# backplane.net
KiCad netlist of a schematic drawn in EAGLE
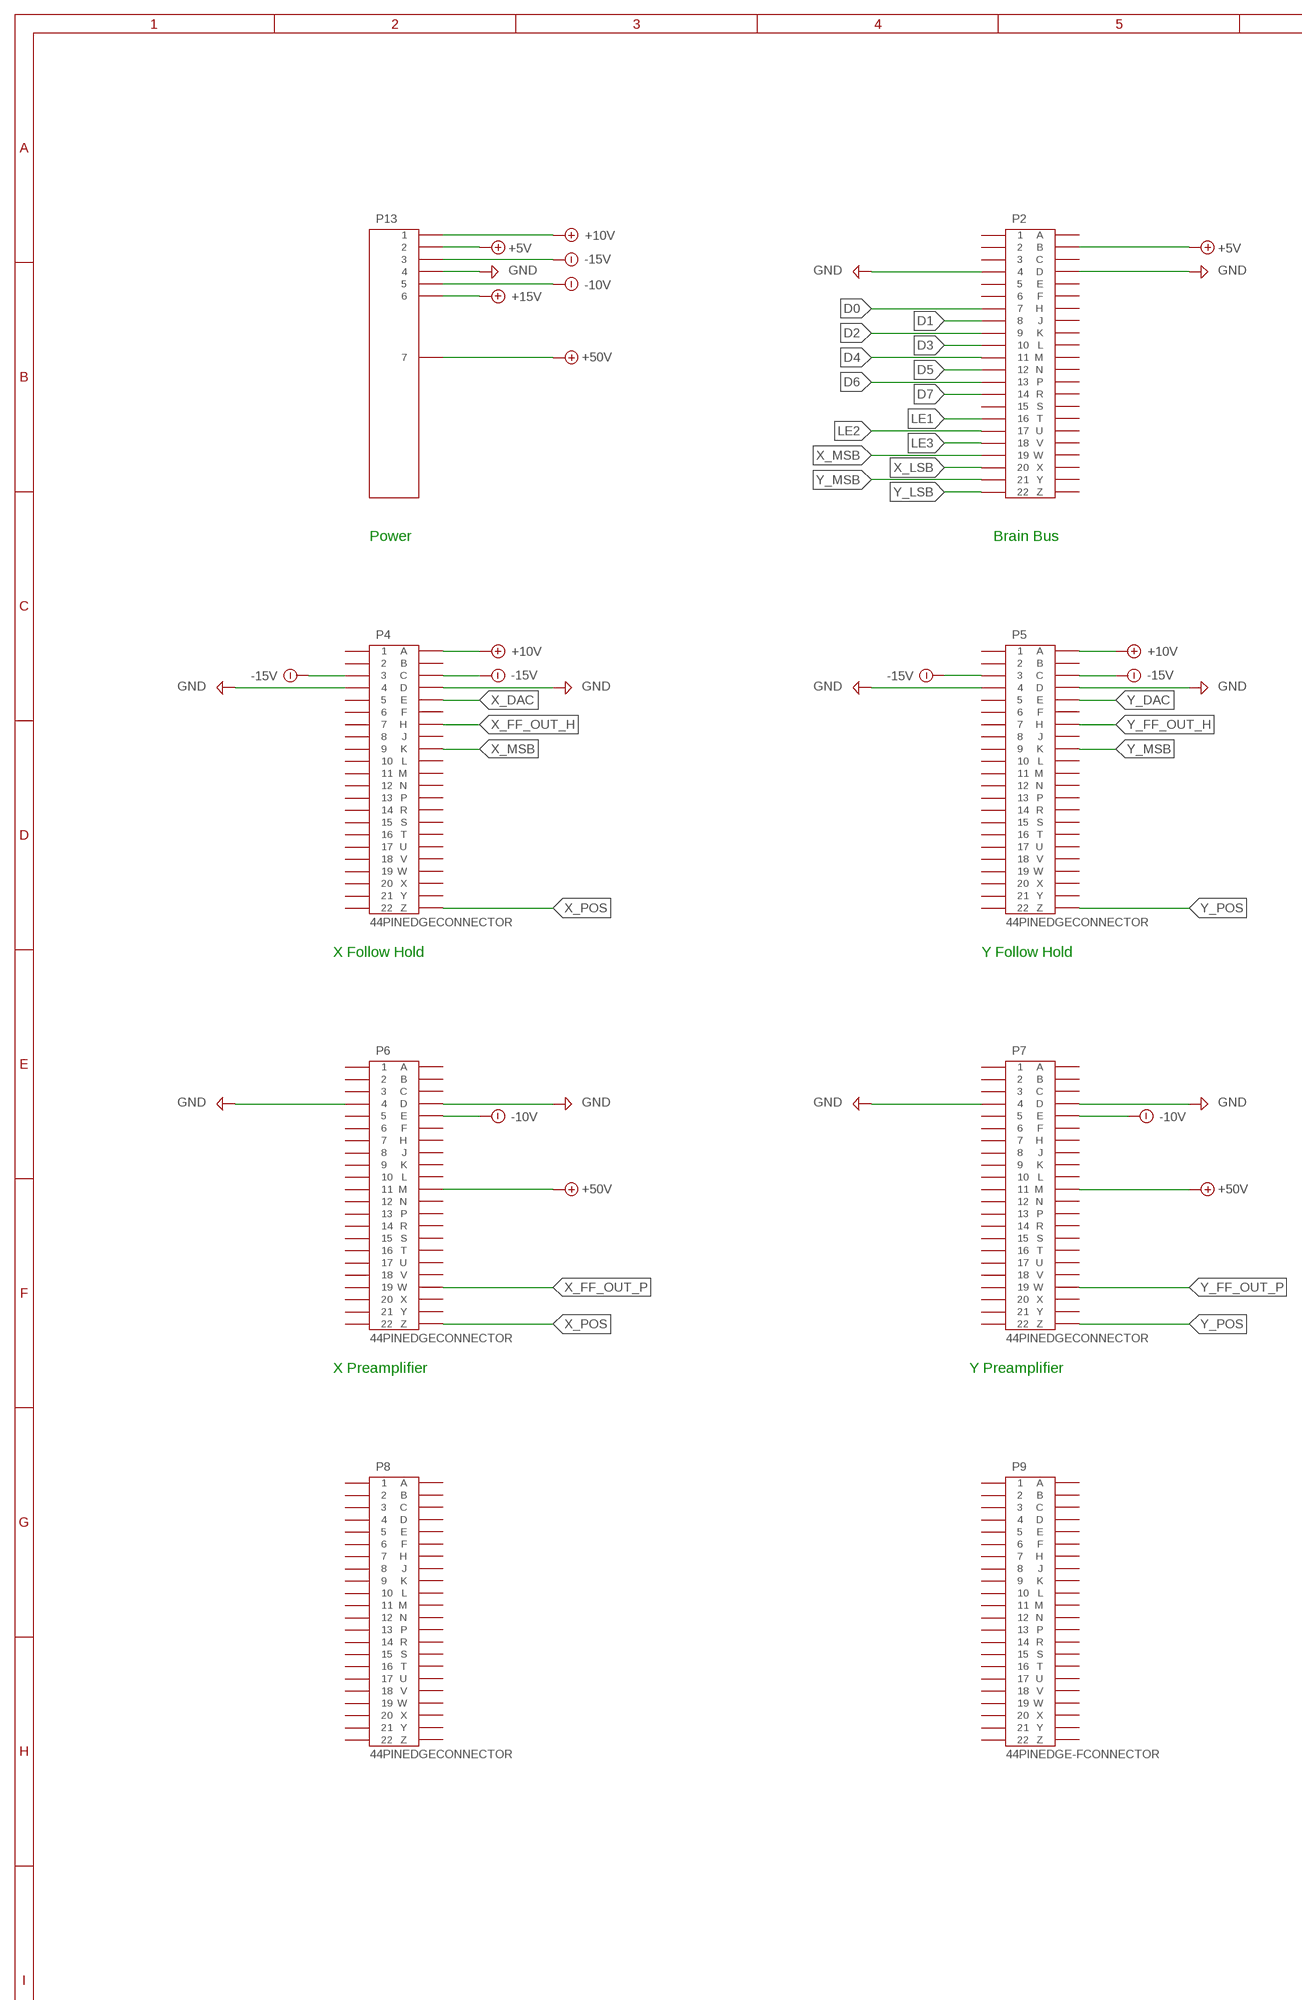
[diagram p0: schematic, sheet 1, part 1 of 2]
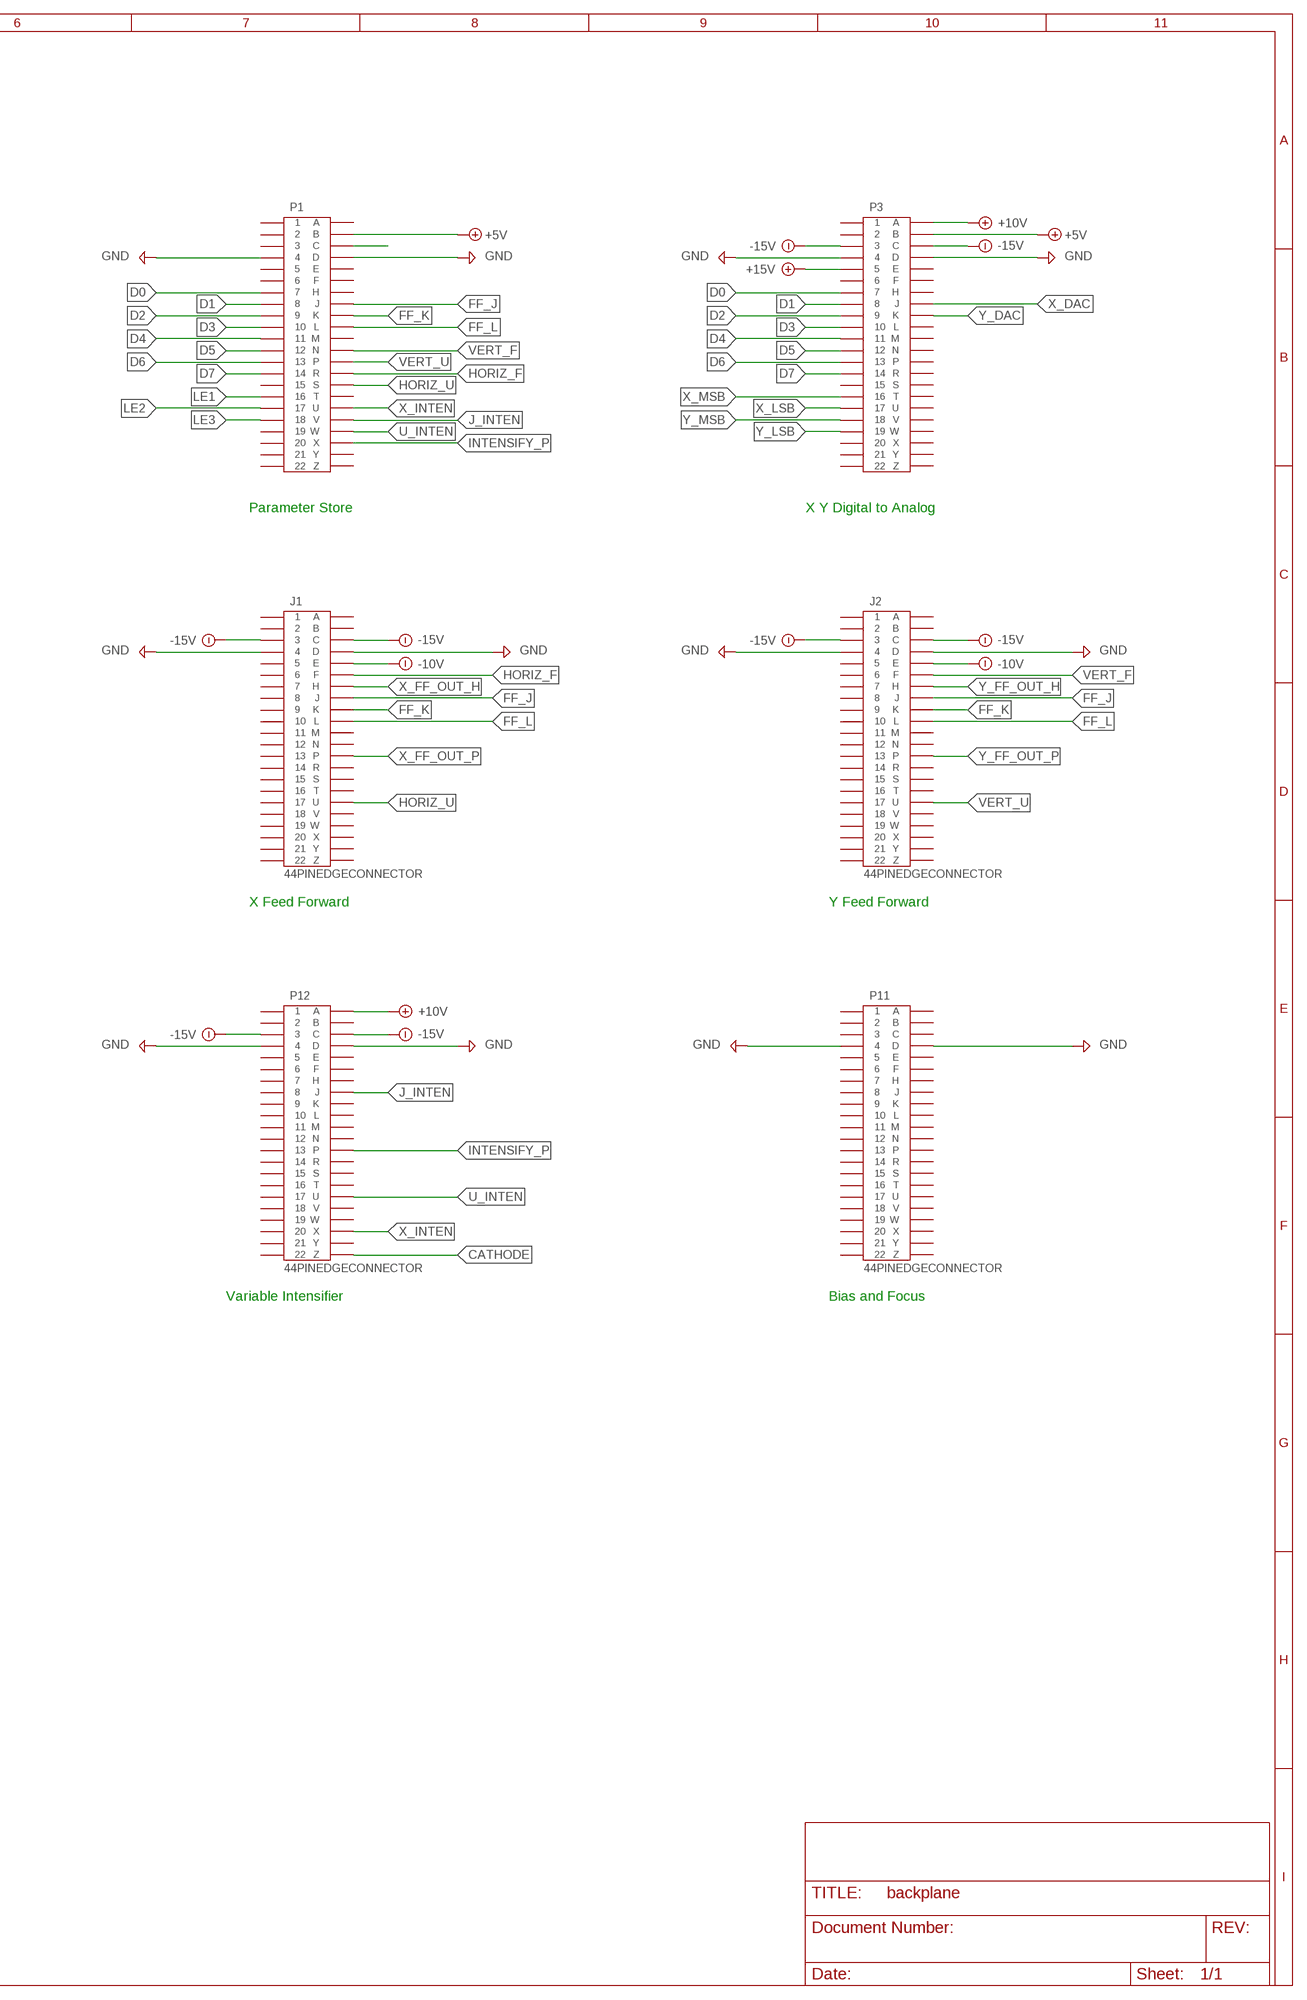
[diagram p1: schematic, sheet 1, part 2 of 2]

(export (version "E")
  (design (tool "Eeschema 10.0.6"))
  (components
    (comp (ref "J1")
      (value "44PINEDGECONNECTOR")
      (footprint "eagle-import:44PINEDGECONN")
      (libsource (lib "eagle-import") (part "44PINEDGECONNECTOR"))
    )
    (comp (ref "J2")
      (value "44PINEDGECONNECTOR")
      (footprint "eagle-import:44PINEDGECONN")
      (libsource (lib "eagle-import") (part "44PINEDGECONNECTOR"))
    )
    (comp (ref "P1")
      (value "44PINEDGECONNECTOR")
      (footprint "eagle-import:44PINEDGECONN")
      (libsource (lib "eagle-import") (part "44PINEDGECONNECTOR"))
    )
    (comp (ref "P2")
      (value "44PINEDGECONNECTOR")
      (footprint "eagle-import:44PINEDGECONN")
      (libsource (lib "eagle-import") (part "44PINEDGECONNECTOR"))
    )
    (comp (ref "P3")
      (value "44PINEDGECONNECTOR")
      (footprint "eagle-import:44PINEDGECONN")
      (libsource (lib "eagle-import") (part "44PINEDGECONNECTOR"))
    )
    (comp (ref "P4")
      (value "44PINEDGECONNECTOR")
      (footprint "eagle-import:44PINEDGECONN")
      (libsource (lib "eagle-import") (part "44PINEDGECONNECTOR"))
    )
    (comp (ref "P5")
      (value "44PINEDGECONNECTOR")
      (footprint "eagle-import:44PINEDGECONN")
      (libsource (lib "eagle-import") (part "44PINEDGECONNECTOR"))
    )
    (comp (ref "P6")
      (value "44PINEDGECONNECTOR")
      (footprint "eagle-import:44PINEDGECONN")
      (libsource (lib "eagle-import") (part "44PINEDGECONNECTOR"))
    )
    (comp (ref "P7")
      (value "44PINEDGECONNECTOR")
      (footprint "eagle-import:44PINEDGECONN")
      (libsource (lib "eagle-import") (part "44PINEDGECONNECTOR"))
    )
    (comp (ref "P8")
      (value "44PINEDGECONNECTOR")
      (footprint "eagle-import:44PINEDGECONN")
      (libsource (lib "eagle-import") (part "44PINEDGECONNECTOR"))
    )
    (comp (ref "P9")
      (value "44PINEDGE-FCONNECTOR")
      (footprint "eagle-import:44PINEDGECONN")
      (libsource (lib "eagle-import") (part "44PINEDGE-FCONNECTOR"))
    )
    (comp (ref "P11")
      (value "44PINEDGECONNECTOR")
      (footprint "eagle-import:44PINEDGECONN")
      (libsource (lib "eagle-import") (part "44PINEDGECONNECTOR"))
    )
    (comp (ref "P12")
      (value "44PINEDGECONNECTOR")
      (footprint "eagle-import:44PINEDGECONN")
      (libsource (lib "eagle-import") (part "44PINEDGECONNECTOR"))
    )
    (comp (ref "P13")
      (value "PASSTHROUGH")
      (footprint "eagle-import:PASSTHROUGH")
      (libsource (lib "eagle-import") (part "PASSTHROUGH"))
    )
  )
  (nets
    (net (code "1") (name "+5V") (class "Default")
      (node (ref "P1") (pin "P$24") (pinfunction "B_P$24") (pintype "passive"))
      (node (ref "P13") (pin "P$2") (pinfunction "2_P$2") (pintype "passive"))
      (node (ref "P2") (pin "P$24") (pinfunction "B_P$24") (pintype "passive"))
      (node (ref "P3") (pin "P$24") (pinfunction "B_P$24") (pintype "passive"))
    )
    (net (code "2") (name "+10V") (class "Default")
      (node (ref "P12") (pin "P$23") (pinfunction "A_P$23") (pintype "passive"))
      (node (ref "P13") (pin "P$1") (pinfunction "1_P$1") (pintype "passive"))
      (node (ref "P3") (pin "P$23") (pinfunction "A_P$23") (pintype "passive"))
      (node (ref "P4") (pin "P$23") (pinfunction "A_P$23") (pintype "passive"))
      (node (ref "P5") (pin "P$23") (pinfunction "A_P$23") (pintype "passive"))
    )
    (net (code "3") (name "+15V") (class "Default")
      (node (ref "P13") (pin "P$6") (pinfunction "6_P$6") (pintype "passive"))
      (node (ref "P3") (pin "P$5") (pinfunction "5_P$5") (pintype "passive"))
    )
    (net (code "4") (name "+50V") (class "Default")
      (node (ref "P13") (pin "P$7") (pinfunction "7_P$7") (pintype "passive"))
      (node (ref "P6") (pin "P$33") (pinfunction "M_P$33") (pintype "passive"))
      (node (ref "P7") (pin "P$33") (pinfunction "M_P$33") (pintype "passive"))
    )
    (net (code "5") (name "-10V") (class "Default")
      (node (ref "J1") (pin "P$27") (pinfunction "E_P$27") (pintype "passive"))
      (node (ref "J2") (pin "P$27") (pinfunction "E_P$27") (pintype "passive"))
      (node (ref "P13") (pin "P$5") (pinfunction "5_P$5") (pintype "passive"))
      (node (ref "P6") (pin "P$27") (pinfunction "E_P$27") (pintype "passive"))
      (node (ref "P7") (pin "P$27") (pinfunction "E_P$27") (pintype "passive"))
    )
    (net (code "6") (name "-15V") (class "Default")
      (node (ref "J1") (pin "P$25") (pinfunction "C_P$25") (pintype "passive"))
      (node (ref "J1") (pin "P$3") (pinfunction "3_P$3") (pintype "passive"))
      (node (ref "J2") (pin "P$25") (pinfunction "C_P$25") (pintype "passive"))
      (node (ref "J2") (pin "P$3") (pinfunction "3_P$3") (pintype "passive"))
      (node (ref "P12") (pin "P$25") (pinfunction "C_P$25") (pintype "passive"))
      (node (ref "P12") (pin "P$3") (pinfunction "3_P$3") (pintype "passive"))
      (node (ref "P13") (pin "P$3") (pinfunction "3_P$3") (pintype "passive"))
      (node (ref "P3") (pin "P$25") (pinfunction "C_P$25") (pintype "passive"))
      (node (ref "P3") (pin "P$3") (pinfunction "3_P$3") (pintype "passive"))
      (node (ref "P4") (pin "P$25") (pinfunction "C_P$25") (pintype "passive"))
      (node (ref "P4") (pin "P$3") (pinfunction "3_P$3") (pintype "passive"))
      (node (ref "P5") (pin "P$25") (pinfunction "C_P$25") (pintype "passive"))
      (node (ref "P5") (pin "P$3") (pinfunction "3_P$3") (pintype "passive"))
    )
    (net (code "7") (name "CATHODE") (class "Default")
      (node (ref "P12") (pin "P$44") (pinfunction "Z_P$44") (pintype "passive"))
    )
    (net (code "8") (name "D0") (class "Default")
      (node (ref "P1") (pin "P$7") (pinfunction "7_P$7") (pintype "passive"))
      (node (ref "P2") (pin "P$7") (pinfunction "7_P$7") (pintype "passive"))
      (node (ref "P3") (pin "P$7") (pinfunction "7_P$7") (pintype "passive"))
    )
    (net (code "9") (name "D1") (class "Default")
      (node (ref "P1") (pin "P$8") (pinfunction "8_P$8") (pintype "passive"))
      (node (ref "P2") (pin "P$8") (pinfunction "8_P$8") (pintype "passive"))
      (node (ref "P3") (pin "P$8") (pinfunction "8_P$8") (pintype "passive"))
    )
    (net (code "10") (name "D2") (class "Default")
      (node (ref "P1") (pin "P$9") (pinfunction "9_P$9") (pintype "passive"))
      (node (ref "P2") (pin "P$9") (pinfunction "9_P$9") (pintype "passive"))
      (node (ref "P3") (pin "P$9") (pinfunction "9_P$9") (pintype "passive"))
    )
    (net (code "11") (name "D3") (class "Default")
      (node (ref "P1") (pin "P$10") (pinfunction "10_P$10") (pintype "passive"))
      (node (ref "P2") (pin "P$10") (pinfunction "10_P$10") (pintype "passive"))
      (node (ref "P3") (pin "P$10") (pinfunction "10_P$10") (pintype "passive"))
    )
    (net (code "12") (name "D4") (class "Default")
      (node (ref "P1") (pin "P$11") (pinfunction "11_P$11") (pintype "passive"))
      (node (ref "P2") (pin "P$11") (pinfunction "11_P$11") (pintype "passive"))
      (node (ref "P3") (pin "P$11") (pinfunction "11_P$11") (pintype "passive"))
    )
    (net (code "13") (name "D5") (class "Default")
      (node (ref "P1") (pin "P$12") (pinfunction "12_P$12") (pintype "passive"))
      (node (ref "P2") (pin "P$12") (pinfunction "12_P$12") (pintype "passive"))
      (node (ref "P3") (pin "P$12") (pinfunction "12_P$12") (pintype "passive"))
    )
    (net (code "14") (name "D6") (class "Default")
      (node (ref "P1") (pin "P$13") (pinfunction "13_P$13") (pintype "passive"))
      (node (ref "P2") (pin "P$13") (pinfunction "13_P$13") (pintype "passive"))
      (node (ref "P3") (pin "P$13") (pinfunction "13_P$13") (pintype "passive"))
    )
    (net (code "15") (name "D7") (class "Default")
      (node (ref "P1") (pin "P$14") (pinfunction "14_P$14") (pintype "passive"))
      (node (ref "P2") (pin "P$14") (pinfunction "14_P$14") (pintype "passive"))
      (node (ref "P3") (pin "P$14") (pinfunction "14_P$14") (pintype "passive"))
    )
    (net (code "16") (name "FF_J") (class "Default")
      (node (ref "J1") (pin "P$30") (pinfunction "J_P$30") (pintype "passive"))
      (node (ref "J2") (pin "P$30") (pinfunction "J_P$30") (pintype "passive"))
      (node (ref "P1") (pin "P$30") (pinfunction "J_P$30") (pintype "passive"))
    )
    (net (code "17") (name "FF_K") (class "Default")
      (node (ref "J1") (pin "P$31") (pinfunction "K_P$31") (pintype "passive"))
      (node (ref "J2") (pin "P$31") (pinfunction "K_P$31") (pintype "passive"))
      (node (ref "P1") (pin "P$31") (pinfunction "K_P$31") (pintype "passive"))
    )
    (net (code "18") (name "FF_L") (class "Default")
      (node (ref "J1") (pin "P$32") (pinfunction "L_P$32") (pintype "passive"))
      (node (ref "J2") (pin "P$32") (pinfunction "L_P$32") (pintype "passive"))
      (node (ref "P1") (pin "P$32") (pinfunction "L_P$32") (pintype "passive"))
    )
    (net (code "19") (name "GND") (class "Default")
      (node (ref "J1") (pin "P$26") (pinfunction "D_P$26") (pintype "passive"))
      (node (ref "J1") (pin "P$4") (pinfunction "4_P$4") (pintype "passive"))
      (node (ref "J2") (pin "P$26") (pinfunction "D_P$26") (pintype "passive"))
      (node (ref "J2") (pin "P$4") (pinfunction "4_P$4") (pintype "passive"))
      (node (ref "P1") (pin "P$26") (pinfunction "D_P$26") (pintype "passive"))
      (node (ref "P1") (pin "P$4") (pinfunction "4_P$4") (pintype "passive"))
      (node (ref "P11") (pin "P$26") (pinfunction "D_P$26") (pintype "passive"))
      (node (ref "P11") (pin "P$4") (pinfunction "4_P$4") (pintype "passive"))
      (node (ref "P12") (pin "P$26") (pinfunction "D_P$26") (pintype "passive"))
      (node (ref "P12") (pin "P$4") (pinfunction "4_P$4") (pintype "passive"))
      (node (ref "P13") (pin "P$4") (pinfunction "4_P$4") (pintype "passive"))
      (node (ref "P2") (pin "P$26") (pinfunction "D_P$26") (pintype "passive"))
      (node (ref "P2") (pin "P$4") (pinfunction "4_P$4") (pintype "passive"))
      (node (ref "P3") (pin "P$26") (pinfunction "D_P$26") (pintype "passive"))
      (node (ref "P3") (pin "P$4") (pinfunction "4_P$4") (pintype "passive"))
      (node (ref "P4") (pin "P$26") (pinfunction "D_P$26") (pintype "passive"))
      (node (ref "P4") (pin "P$4") (pinfunction "4_P$4") (pintype "passive"))
      (node (ref "P5") (pin "P$26") (pinfunction "D_P$26") (pintype "passive"))
      (node (ref "P5") (pin "P$4") (pinfunction "4_P$4") (pintype "passive"))
      (node (ref "P6") (pin "P$26") (pinfunction "D_P$26") (pintype "passive"))
      (node (ref "P6") (pin "P$4") (pinfunction "4_P$4") (pintype "passive"))
      (node (ref "P7") (pin "P$26") (pinfunction "D_P$26") (pintype "passive"))
      (node (ref "P7") (pin "P$4") (pinfunction "4_P$4") (pintype "passive"))
    )
    (net (code "20") (name "HORIZ_F") (class "Default")
      (node (ref "J1") (pin "P$28") (pinfunction "F_P$28") (pintype "passive"))
      (node (ref "P1") (pin "P$36") (pinfunction "R_P$36") (pintype "passive"))
    )
    (net (code "21") (name "HORIZ_U") (class "Default")
      (node (ref "J1") (pin "P$39") (pinfunction "U_P$39") (pintype "passive"))
      (node (ref "P1") (pin "P$37") (pinfunction "S_P$37") (pintype "passive"))
    )
    (net (code "22") (name "INTENSIFY_P") (class "Default")
      (node (ref "P1") (pin "P$42") (pinfunction "X_P$42") (pintype "passive"))
      (node (ref "P12") (pin "P$35") (pinfunction "P_P$35") (pintype "passive"))
    )
    (net (code "23") (name "J_INTEN") (class "Default")
      (node (ref "P1") (pin "P$40") (pinfunction "V_P$40") (pintype "passive"))
      (node (ref "P12") (pin "P$30") (pinfunction "J_P$30") (pintype "passive"))
    )
    (net (code "24") (name "LE1") (class "Default")
      (node (ref "P1") (pin "P$16") (pinfunction "16_P$16") (pintype "passive"))
      (node (ref "P2") (pin "P$16") (pinfunction "16_P$16") (pintype "passive"))
    )
    (net (code "25") (name "LE2") (class "Default")
      (node (ref "P1") (pin "P$17") (pinfunction "17_P$17") (pintype "passive"))
      (node (ref "P2") (pin "P$17") (pinfunction "17_P$17") (pintype "passive"))
    )
    (net (code "26") (name "LE3") (class "Default")
      (node (ref "P1") (pin "P$18") (pinfunction "18_P$18") (pintype "passive"))
      (node (ref "P2") (pin "P$18") (pinfunction "18_P$18") (pintype "passive"))
    )
    (net (code "27") (name "U_INTEN") (class "Default")
      (node (ref "P1") (pin "P$41") (pinfunction "W_P$41") (pintype "passive"))
      (node (ref "P12") (pin "P$39") (pinfunction "U_P$39") (pintype "passive"))
    )
    (net (code "28") (name "VERT_F") (class "Default")
      (node (ref "J2") (pin "P$28") (pinfunction "F_P$28") (pintype "passive"))
      (node (ref "P1") (pin "P$34") (pinfunction "N_P$34") (pintype "passive"))
    )
    (net (code "29") (name "VERT_U") (class "Default")
      (node (ref "J2") (pin "P$39") (pinfunction "U_P$39") (pintype "passive"))
      (node (ref "P1") (pin "P$35") (pinfunction "P_P$35") (pintype "passive"))
    )
    (net (code "30") (name "X_DAC") (class "Default")
      (node (ref "P3") (pin "P$30") (pinfunction "J_P$30") (pintype "passive"))
      (node (ref "P4") (pin "P$27") (pinfunction "E_P$27") (pintype "passive"))
    )
    (net (code "31") (name "X_FF_OUT_H") (class "Default")
      (node (ref "J1") (pin "P$29") (pinfunction "H_P$29") (pintype "passive"))
      (node (ref "P4") (pin "P$29") (pinfunction "H_P$29") (pintype "passive"))
    )
    (net (code "32") (name "X_FF_OUT_P") (class "Default")
      (node (ref "J1") (pin "P$35") (pinfunction "P_P$35") (pintype "passive"))
      (node (ref "P6") (pin "P$41") (pinfunction "W_P$41") (pintype "passive"))
    )
    (net (code "33") (name "X_INTEN") (class "Default")
      (node (ref "P1") (pin "P$39") (pinfunction "U_P$39") (pintype "passive"))
      (node (ref "P12") (pin "P$42") (pinfunction "X_P$42") (pintype "passive"))
    )
    (net (code "34") (name "X_LSB") (class "Default")
      (node (ref "P2") (pin "P$20") (pinfunction "20_P$20") (pintype "passive"))
      (node (ref "P3") (pin "P$17") (pinfunction "17_P$17") (pintype "passive"))
    )
    (net (code "35") (name "X_MSB") (class "Default")
      (node (ref "P2") (pin "P$19") (pinfunction "19_P$19") (pintype "passive"))
      (node (ref "P3") (pin "P$16") (pinfunction "16_P$16") (pintype "passive"))
      (node (ref "P4") (pin "P$31") (pinfunction "K_P$31") (pintype "passive"))
    )
    (net (code "36") (name "X_POS") (class "Default")
      (node (ref "P4") (pin "P$44") (pinfunction "Z_P$44") (pintype "passive"))
      (node (ref "P6") (pin "P$44") (pinfunction "Z_P$44") (pintype "passive"))
    )
    (net (code "37") (name "Y_DAC") (class "Default")
      (node (ref "P3") (pin "P$31") (pinfunction "K_P$31") (pintype "passive"))
      (node (ref "P5") (pin "P$27") (pinfunction "E_P$27") (pintype "passive"))
    )
    (net (code "38") (name "Y_FF_OUT_H") (class "Default")
      (node (ref "J2") (pin "P$29") (pinfunction "H_P$29") (pintype "passive"))
      (node (ref "P5") (pin "P$29") (pinfunction "H_P$29") (pintype "passive"))
    )
    (net (code "39") (name "Y_FF_OUT_P") (class "Default")
      (node (ref "J2") (pin "P$35") (pinfunction "P_P$35") (pintype "passive"))
      (node (ref "P7") (pin "P$41") (pinfunction "W_P$41") (pintype "passive"))
    )
    (net (code "40") (name "Y_LSB") (class "Default")
      (node (ref "P2") (pin "P$22") (pinfunction "22_P$22") (pintype "passive"))
      (node (ref "P3") (pin "P$19") (pinfunction "19_P$19") (pintype "passive"))
    )
    (net (code "41") (name "Y_MSB") (class "Default")
      (node (ref "P2") (pin "P$21") (pinfunction "21_P$21") (pintype "passive"))
      (node (ref "P3") (pin "P$18") (pinfunction "18_P$18") (pintype "passive"))
      (node (ref "P5") (pin "P$31") (pinfunction "K_P$31") (pintype "passive"))
    )
    (net (code "42") (name "Y_POS") (class "Default")
      (node (ref "P5") (pin "P$44") (pinfunction "Z_P$44") (pintype "passive"))
      (node (ref "P7") (pin "P$44") (pinfunction "Z_P$44") (pintype "passive"))
    )
    (net (code "43") (name "unconnected-(J1-1-PadP$1)") (class "Default")
      (node (ref "J1") (pin "P$1") (pinfunction "1_P$1") (pintype "passive"))
    )
    (net (code "44") (name "unconnected-(J1-2-PadP$2)") (class "Default")
      (node (ref "J1") (pin "P$2") (pinfunction "2_P$2") (pintype "passive"))
    )
    (net (code "45") (name "unconnected-(J1-5-PadP$5)") (class "Default")
      (node (ref "J1") (pin "P$5") (pinfunction "5_P$5") (pintype "passive"))
    )
    (net (code "46") (name "unconnected-(J1-6-PadP$6)") (class "Default")
      (node (ref "J1") (pin "P$6") (pinfunction "6_P$6") (pintype "passive"))
    )
    (net (code "47") (name "unconnected-(J1-7-PadP$7)") (class "Default")
      (node (ref "J1") (pin "P$7") (pinfunction "7_P$7") (pintype "passive"))
    )
    (net (code "48") (name "unconnected-(J1-8-PadP$8)") (class "Default")
      (node (ref "J1") (pin "P$8") (pinfunction "8_P$8") (pintype "passive"))
    )
    (net (code "49") (name "unconnected-(J1-9-PadP$9)") (class "Default")
      (node (ref "J1") (pin "P$9") (pinfunction "9_P$9") (pintype "passive"))
    )
    (net (code "50") (name "unconnected-(J1-10-PadP$10)") (class "Default")
      (node (ref "J1") (pin "P$10") (pinfunction "10_P$10") (pintype "passive"))
    )
    (net (code "51") (name "unconnected-(J1-11-PadP$11)") (class "Default")
      (node (ref "J1") (pin "P$11") (pinfunction "11_P$11") (pintype "passive"))
    )
    (net (code "52") (name "unconnected-(J1-12-PadP$12)") (class "Default")
      (node (ref "J1") (pin "P$12") (pinfunction "12_P$12") (pintype "passive"))
    )
    (net (code "53") (name "unconnected-(J1-13-PadP$13)") (class "Default")
      (node (ref "J1") (pin "P$13") (pinfunction "13_P$13") (pintype "passive"))
    )
    (net (code "54") (name "unconnected-(J1-14-PadP$14)") (class "Default")
      (node (ref "J1") (pin "P$14") (pinfunction "14_P$14") (pintype "passive"))
    )
    (net (code "55") (name "unconnected-(J1-15-PadP$15)") (class "Default")
      (node (ref "J1") (pin "P$15") (pinfunction "15_P$15") (pintype "passive"))
    )
    (net (code "56") (name "unconnected-(J1-16-PadP$16)") (class "Default")
      (node (ref "J1") (pin "P$16") (pinfunction "16_P$16") (pintype "passive"))
    )
    (net (code "57") (name "unconnected-(J1-17-PadP$17)") (class "Default")
      (node (ref "J1") (pin "P$17") (pinfunction "17_P$17") (pintype "passive"))
    )
    (net (code "58") (name "unconnected-(J1-18-PadP$18)") (class "Default")
      (node (ref "J1") (pin "P$18") (pinfunction "18_P$18") (pintype "passive"))
    )
    (net (code "59") (name "unconnected-(J1-19-PadP$19)") (class "Default")
      (node (ref "J1") (pin "P$19") (pinfunction "19_P$19") (pintype "passive"))
    )
    (net (code "60") (name "unconnected-(J1-20-PadP$20)") (class "Default")
      (node (ref "J1") (pin "P$20") (pinfunction "20_P$20") (pintype "passive"))
    )
    (net (code "61") (name "unconnected-(J1-21-PadP$21)") (class "Default")
      (node (ref "J1") (pin "P$21") (pinfunction "21_P$21") (pintype "passive"))
    )
    (net (code "62") (name "unconnected-(J1-22-PadP$22)") (class "Default")
      (node (ref "J1") (pin "P$22") (pinfunction "22_P$22") (pintype "passive"))
    )
    (net (code "63") (name "unconnected-(J1-A-PadP$23)") (class "Default")
      (node (ref "J1") (pin "P$23") (pinfunction "A_P$23") (pintype "passive"))
    )
    (net (code "64") (name "unconnected-(J1-B-PadP$24)") (class "Default")
      (node (ref "J1") (pin "P$24") (pinfunction "B_P$24") (pintype "passive"))
    )
    (net (code "65") (name "unconnected-(J1-M-PadP$33)") (class "Default")
      (node (ref "J1") (pin "P$33") (pinfunction "M_P$33") (pintype "passive"))
    )
    (net (code "66") (name "unconnected-(J1-N-PadP$34)") (class "Default")
      (node (ref "J1") (pin "P$34") (pinfunction "N_P$34") (pintype "passive"))
    )
    (net (code "67") (name "unconnected-(J1-R-PadP$36)") (class "Default")
      (node (ref "J1") (pin "P$36") (pinfunction "R_P$36") (pintype "passive"))
    )
    (net (code "68") (name "unconnected-(J1-S-PadP$37)") (class "Default")
      (node (ref "J1") (pin "P$37") (pinfunction "S_P$37") (pintype "passive"))
    )
    (net (code "69") (name "unconnected-(J1-T-PadP$38)") (class "Default")
      (node (ref "J1") (pin "P$38") (pinfunction "T_P$38") (pintype "passive"))
    )
    (net (code "70") (name "unconnected-(J1-V-PadP$40)") (class "Default")
      (node (ref "J1") (pin "P$40") (pinfunction "V_P$40") (pintype "passive"))
    )
    (net (code "71") (name "unconnected-(J1-W-PadP$41)") (class "Default")
      (node (ref "J1") (pin "P$41") (pinfunction "W_P$41") (pintype "passive"))
    )
    (net (code "72") (name "unconnected-(J1-X-PadP$42)") (class "Default")
      (node (ref "J1") (pin "P$42") (pinfunction "X_P$42") (pintype "passive"))
    )
    (net (code "73") (name "unconnected-(J1-Y-PadP$43)") (class "Default")
      (node (ref "J1") (pin "P$43") (pinfunction "Y_P$43") (pintype "passive"))
    )
    (net (code "74") (name "unconnected-(J1-Z-PadP$44)") (class "Default")
      (node (ref "J1") (pin "P$44") (pinfunction "Z_P$44") (pintype "passive"))
    )
    (net (code "75") (name "unconnected-(J2-1-PadP$1)") (class "Default")
      (node (ref "J2") (pin "P$1") (pinfunction "1_P$1") (pintype "passive"))
    )
    (net (code "76") (name "unconnected-(J2-2-PadP$2)") (class "Default")
      (node (ref "J2") (pin "P$2") (pinfunction "2_P$2") (pintype "passive"))
    )
    (net (code "77") (name "unconnected-(J2-5-PadP$5)") (class "Default")
      (node (ref "J2") (pin "P$5") (pinfunction "5_P$5") (pintype "passive"))
    )
    (net (code "78") (name "unconnected-(J2-6-PadP$6)") (class "Default")
      (node (ref "J2") (pin "P$6") (pinfunction "6_P$6") (pintype "passive"))
    )
    (net (code "79") (name "unconnected-(J2-7-PadP$7)") (class "Default")
      (node (ref "J2") (pin "P$7") (pinfunction "7_P$7") (pintype "passive"))
    )
    (net (code "80") (name "unconnected-(J2-8-PadP$8)") (class "Default")
      (node (ref "J2") (pin "P$8") (pinfunction "8_P$8") (pintype "passive"))
    )
    (net (code "81") (name "unconnected-(J2-9-PadP$9)") (class "Default")
      (node (ref "J2") (pin "P$9") (pinfunction "9_P$9") (pintype "passive"))
    )
    (net (code "82") (name "unconnected-(J2-10-PadP$10)") (class "Default")
      (node (ref "J2") (pin "P$10") (pinfunction "10_P$10") (pintype "passive"))
    )
    (net (code "83") (name "unconnected-(J2-11-PadP$11)") (class "Default")
      (node (ref "J2") (pin "P$11") (pinfunction "11_P$11") (pintype "passive"))
    )
    (net (code "84") (name "unconnected-(J2-12-PadP$12)") (class "Default")
      (node (ref "J2") (pin "P$12") (pinfunction "12_P$12") (pintype "passive"))
    )
    (net (code "85") (name "unconnected-(J2-13-PadP$13)") (class "Default")
      (node (ref "J2") (pin "P$13") (pinfunction "13_P$13") (pintype "passive"))
    )
    (net (code "86") (name "unconnected-(J2-14-PadP$14)") (class "Default")
      (node (ref "J2") (pin "P$14") (pinfunction "14_P$14") (pintype "passive"))
    )
    (net (code "87") (name "unconnected-(J2-15-PadP$15)") (class "Default")
      (node (ref "J2") (pin "P$15") (pinfunction "15_P$15") (pintype "passive"))
    )
    (net (code "88") (name "unconnected-(J2-16-PadP$16)") (class "Default")
      (node (ref "J2") (pin "P$16") (pinfunction "16_P$16") (pintype "passive"))
    )
    (net (code "89") (name "unconnected-(J2-17-PadP$17)") (class "Default")
      (node (ref "J2") (pin "P$17") (pinfunction "17_P$17") (pintype "passive"))
    )
    (net (code "90") (name "unconnected-(J2-18-PadP$18)") (class "Default")
      (node (ref "J2") (pin "P$18") (pinfunction "18_P$18") (pintype "passive"))
    )
    (net (code "91") (name "unconnected-(J2-19-PadP$19)") (class "Default")
      (node (ref "J2") (pin "P$19") (pinfunction "19_P$19") (pintype "passive"))
    )
    (net (code "92") (name "unconnected-(J2-20-PadP$20)") (class "Default")
      (node (ref "J2") (pin "P$20") (pinfunction "20_P$20") (pintype "passive"))
    )
    (net (code "93") (name "unconnected-(J2-21-PadP$21)") (class "Default")
      (node (ref "J2") (pin "P$21") (pinfunction "21_P$21") (pintype "passive"))
    )
    (net (code "94") (name "unconnected-(J2-22-PadP$22)") (class "Default")
      (node (ref "J2") (pin "P$22") (pinfunction "22_P$22") (pintype "passive"))
    )
    (net (code "95") (name "unconnected-(J2-A-PadP$23)") (class "Default")
      (node (ref "J2") (pin "P$23") (pinfunction "A_P$23") (pintype "passive"))
    )
    (net (code "96") (name "unconnected-(J2-B-PadP$24)") (class "Default")
      (node (ref "J2") (pin "P$24") (pinfunction "B_P$24") (pintype "passive"))
    )
    (net (code "97") (name "unconnected-(J2-M-PadP$33)") (class "Default")
      (node (ref "J2") (pin "P$33") (pinfunction "M_P$33") (pintype "passive"))
    )
    (net (code "98") (name "unconnected-(J2-N-PadP$34)") (class "Default")
      (node (ref "J2") (pin "P$34") (pinfunction "N_P$34") (pintype "passive"))
    )
    (net (code "99") (name "unconnected-(J2-R-PadP$36)") (class "Default")
      (node (ref "J2") (pin "P$36") (pinfunction "R_P$36") (pintype "passive"))
    )
    (net (code "100") (name "unconnected-(J2-S-PadP$37)") (class "Default")
      (node (ref "J2") (pin "P$37") (pinfunction "S_P$37") (pintype "passive"))
    )
    (net (code "101") (name "unconnected-(J2-T-PadP$38)") (class "Default")
      (node (ref "J2") (pin "P$38") (pinfunction "T_P$38") (pintype "passive"))
    )
    (net (code "102") (name "unconnected-(J2-V-PadP$40)") (class "Default")
      (node (ref "J2") (pin "P$40") (pinfunction "V_P$40") (pintype "passive"))
    )
    (net (code "103") (name "unconnected-(J2-W-PadP$41)") (class "Default")
      (node (ref "J2") (pin "P$41") (pinfunction "W_P$41") (pintype "passive"))
    )
    (net (code "104") (name "unconnected-(J2-X-PadP$42)") (class "Default")
      (node (ref "J2") (pin "P$42") (pinfunction "X_P$42") (pintype "passive"))
    )
    (net (code "105") (name "unconnected-(J2-Y-PadP$43)") (class "Default")
      (node (ref "J2") (pin "P$43") (pinfunction "Y_P$43") (pintype "passive"))
    )
    (net (code "106") (name "unconnected-(J2-Z-PadP$44)") (class "Default")
      (node (ref "J2") (pin "P$44") (pinfunction "Z_P$44") (pintype "passive"))
    )
    (net (code "107") (name "unconnected-(P1-1-PadP$1)") (class "Default")
      (node (ref "P1") (pin "P$1") (pinfunction "1_P$1") (pintype "passive"))
    )
    (net (code "108") (name "unconnected-(P1-2-PadP$2)") (class "Default")
      (node (ref "P1") (pin "P$2") (pinfunction "2_P$2") (pintype "passive"))
    )
    (net (code "109") (name "unconnected-(P1-3-PadP$3)") (class "Default")
      (node (ref "P1") (pin "P$3") (pinfunction "3_P$3") (pintype "passive"))
    )
    (net (code "110") (name "unconnected-(P1-5-PadP$5)") (class "Default")
      (node (ref "P1") (pin "P$5") (pinfunction "5_P$5") (pintype "passive"))
    )
    (net (code "111") (name "unconnected-(P1-6-PadP$6)") (class "Default")
      (node (ref "P1") (pin "P$6") (pinfunction "6_P$6") (pintype "passive"))
    )
    (net (code "112") (name "unconnected-(P1-15-PadP$15)") (class "Default")
      (node (ref "P1") (pin "P$15") (pinfunction "15_P$15") (pintype "passive"))
    )
    (net (code "113") (name "unconnected-(P1-19-PadP$19)") (class "Default")
      (node (ref "P1") (pin "P$19") (pinfunction "19_P$19") (pintype "passive"))
    )
    (net (code "114") (name "unconnected-(P1-20-PadP$20)") (class "Default")
      (node (ref "P1") (pin "P$20") (pinfunction "20_P$20") (pintype "passive"))
    )
    (net (code "115") (name "unconnected-(P1-21-PadP$21)") (class "Default")
      (node (ref "P1") (pin "P$21") (pinfunction "21_P$21") (pintype "passive"))
    )
    (net (code "116") (name "unconnected-(P1-22-PadP$22)") (class "Default")
      (node (ref "P1") (pin "P$22") (pinfunction "22_P$22") (pintype "passive"))
    )
    (net (code "117") (name "unconnected-(P1-A-PadP$23)") (class "Default")
      (node (ref "P1") (pin "P$23") (pinfunction "A_P$23") (pintype "passive"))
    )
    (net (code "118") (name "unconnected-(P1-C-PadP$25)") (class "Default")
      (node (ref "P1") (pin "P$25") (pinfunction "C_P$25") (pintype "passive"))
    )
    (net (code "119") (name "unconnected-(P1-E-PadP$27)") (class "Default")
      (node (ref "P1") (pin "P$27") (pinfunction "E_P$27") (pintype "passive"))
    )
    (net (code "120") (name "unconnected-(P1-F-PadP$28)") (class "Default")
      (node (ref "P1") (pin "P$28") (pinfunction "F_P$28") (pintype "passive"))
    )
    (net (code "121") (name "unconnected-(P1-H-PadP$29)") (class "Default")
      (node (ref "P1") (pin "P$29") (pinfunction "H_P$29") (pintype "passive"))
    )
    (net (code "122") (name "unconnected-(P1-M-PadP$33)") (class "Default")
      (node (ref "P1") (pin "P$33") (pinfunction "M_P$33") (pintype "passive"))
    )
    (net (code "123") (name "unconnected-(P1-T-PadP$38)") (class "Default")
      (node (ref "P1") (pin "P$38") (pinfunction "T_P$38") (pintype "passive"))
    )
    (net (code "124") (name "unconnected-(P1-Y-PadP$43)") (class "Default")
      (node (ref "P1") (pin "P$43") (pinfunction "Y_P$43") (pintype "passive"))
    )
    (net (code "125") (name "unconnected-(P1-Z-PadP$44)") (class "Default")
      (node (ref "P1") (pin "P$44") (pinfunction "Z_P$44") (pintype "passive"))
    )
    (net (code "126") (name "unconnected-(P2-1-PadP$1)") (class "Default")
      (node (ref "P2") (pin "P$1") (pinfunction "1_P$1") (pintype "passive"))
    )
    (net (code "127") (name "unconnected-(P2-2-PadP$2)") (class "Default")
      (node (ref "P2") (pin "P$2") (pinfunction "2_P$2") (pintype "passive"))
    )
    (net (code "128") (name "unconnected-(P2-3-PadP$3)") (class "Default")
      (node (ref "P2") (pin "P$3") (pinfunction "3_P$3") (pintype "passive"))
    )
    (net (code "129") (name "unconnected-(P2-5-PadP$5)") (class "Default")
      (node (ref "P2") (pin "P$5") (pinfunction "5_P$5") (pintype "passive"))
    )
    (net (code "130") (name "unconnected-(P2-6-PadP$6)") (class "Default")
      (node (ref "P2") (pin "P$6") (pinfunction "6_P$6") (pintype "passive"))
    )
    (net (code "131") (name "unconnected-(P2-15-PadP$15)") (class "Default")
      (node (ref "P2") (pin "P$15") (pinfunction "15_P$15") (pintype "passive"))
    )
    (net (code "132") (name "unconnected-(P2-A-PadP$23)") (class "Default")
      (node (ref "P2") (pin "P$23") (pinfunction "A_P$23") (pintype "passive"))
    )
    (net (code "133") (name "unconnected-(P2-C-PadP$25)") (class "Default")
      (node (ref "P2") (pin "P$25") (pinfunction "C_P$25") (pintype "passive"))
    )
    (net (code "134") (name "unconnected-(P2-E-PadP$27)") (class "Default")
      (node (ref "P2") (pin "P$27") (pinfunction "E_P$27") (pintype "passive"))
    )
    (net (code "135") (name "unconnected-(P2-F-PadP$28)") (class "Default")
      (node (ref "P2") (pin "P$28") (pinfunction "F_P$28") (pintype "passive"))
    )
    (net (code "136") (name "unconnected-(P2-H-PadP$29)") (class "Default")
      (node (ref "P2") (pin "P$29") (pinfunction "H_P$29") (pintype "passive"))
    )
    (net (code "137") (name "unconnected-(P2-J-PadP$30)") (class "Default")
      (node (ref "P2") (pin "P$30") (pinfunction "J_P$30") (pintype "passive"))
    )
    (net (code "138") (name "unconnected-(P2-K-PadP$31)") (class "Default")
      (node (ref "P2") (pin "P$31") (pinfunction "K_P$31") (pintype "passive"))
    )
    (net (code "139") (name "unconnected-(P2-L-PadP$32)") (class "Default")
      (node (ref "P2") (pin "P$32") (pinfunction "L_P$32") (pintype "passive"))
    )
    (net (code "140") (name "unconnected-(P2-M-PadP$33)") (class "Default")
      (node (ref "P2") (pin "P$33") (pinfunction "M_P$33") (pintype "passive"))
    )
    (net (code "141") (name "unconnected-(P2-N-PadP$34)") (class "Default")
      (node (ref "P2") (pin "P$34") (pinfunction "N_P$34") (pintype "passive"))
    )
    (net (code "142") (name "unconnected-(P2-P-PadP$35)") (class "Default")
      (node (ref "P2") (pin "P$35") (pinfunction "P_P$35") (pintype "passive"))
    )
    (net (code "143") (name "unconnected-(P2-R-PadP$36)") (class "Default")
      (node (ref "P2") (pin "P$36") (pinfunction "R_P$36") (pintype "passive"))
    )
    (net (code "144") (name "unconnected-(P2-S-PadP$37)") (class "Default")
      (node (ref "P2") (pin "P$37") (pinfunction "S_P$37") (pintype "passive"))
    )
    (net (code "145") (name "unconnected-(P2-T-PadP$38)") (class "Default")
      (node (ref "P2") (pin "P$38") (pinfunction "T_P$38") (pintype "passive"))
    )
    (net (code "146") (name "unconnected-(P2-U-PadP$39)") (class "Default")
      (node (ref "P2") (pin "P$39") (pinfunction "U_P$39") (pintype "passive"))
    )
    (net (code "147") (name "unconnected-(P2-V-PadP$40)") (class "Default")
      (node (ref "P2") (pin "P$40") (pinfunction "V_P$40") (pintype "passive"))
    )
    (net (code "148") (name "unconnected-(P2-W-PadP$41)") (class "Default")
      (node (ref "P2") (pin "P$41") (pinfunction "W_P$41") (pintype "passive"))
    )
    (net (code "149") (name "unconnected-(P2-X-PadP$42)") (class "Default")
      (node (ref "P2") (pin "P$42") (pinfunction "X_P$42") (pintype "passive"))
    )
    (net (code "150") (name "unconnected-(P2-Y-PadP$43)") (class "Default")
      (node (ref "P2") (pin "P$43") (pinfunction "Y_P$43") (pintype "passive"))
    )
    (net (code "151") (name "unconnected-(P2-Z-PadP$44)") (class "Default")
      (node (ref "P2") (pin "P$44") (pinfunction "Z_P$44") (pintype "passive"))
    )
    (net (code "152") (name "unconnected-(P3-1-PadP$1)") (class "Default")
      (node (ref "P3") (pin "P$1") (pinfunction "1_P$1") (pintype "passive"))
    )
    (net (code "153") (name "unconnected-(P3-2-PadP$2)") (class "Default")
      (node (ref "P3") (pin "P$2") (pinfunction "2_P$2") (pintype "passive"))
    )
    (net (code "154") (name "unconnected-(P3-6-PadP$6)") (class "Default")
      (node (ref "P3") (pin "P$6") (pinfunction "6_P$6") (pintype "passive"))
    )
    (net (code "155") (name "unconnected-(P3-15-PadP$15)") (class "Default")
      (node (ref "P3") (pin "P$15") (pinfunction "15_P$15") (pintype "passive"))
    )
    (net (code "156") (name "unconnected-(P3-20-PadP$20)") (class "Default")
      (node (ref "P3") (pin "P$20") (pinfunction "20_P$20") (pintype "passive"))
    )
    (net (code "157") (name "unconnected-(P3-21-PadP$21)") (class "Default")
      (node (ref "P3") (pin "P$21") (pinfunction "21_P$21") (pintype "passive"))
    )
    (net (code "158") (name "unconnected-(P3-22-PadP$22)") (class "Default")
      (node (ref "P3") (pin "P$22") (pinfunction "22_P$22") (pintype "passive"))
    )
    (net (code "159") (name "unconnected-(P3-E-PadP$27)") (class "Default")
      (node (ref "P3") (pin "P$27") (pinfunction "E_P$27") (pintype "passive"))
    )
    (net (code "160") (name "unconnected-(P3-F-PadP$28)") (class "Default")
      (node (ref "P3") (pin "P$28") (pinfunction "F_P$28") (pintype "passive"))
    )
    (net (code "161") (name "unconnected-(P3-H-PadP$29)") (class "Default")
      (node (ref "P3") (pin "P$29") (pinfunction "H_P$29") (pintype "passive"))
    )
    (net (code "162") (name "unconnected-(P3-L-PadP$32)") (class "Default")
      (node (ref "P3") (pin "P$32") (pinfunction "L_P$32") (pintype "passive"))
    )
    (net (code "163") (name "unconnected-(P3-M-PadP$33)") (class "Default")
      (node (ref "P3") (pin "P$33") (pinfunction "M_P$33") (pintype "passive"))
    )
    (net (code "164") (name "unconnected-(P3-N-PadP$34)") (class "Default")
      (node (ref "P3") (pin "P$34") (pinfunction "N_P$34") (pintype "passive"))
    )
    (net (code "165") (name "unconnected-(P3-P-PadP$35)") (class "Default")
      (node (ref "P3") (pin "P$35") (pinfunction "P_P$35") (pintype "passive"))
    )
    (net (code "166") (name "unconnected-(P3-R-PadP$36)") (class "Default")
      (node (ref "P3") (pin "P$36") (pinfunction "R_P$36") (pintype "passive"))
    )
    (net (code "167") (name "unconnected-(P3-S-PadP$37)") (class "Default")
      (node (ref "P3") (pin "P$37") (pinfunction "S_P$37") (pintype "passive"))
    )
    (net (code "168") (name "unconnected-(P3-T-PadP$38)") (class "Default")
      (node (ref "P3") (pin "P$38") (pinfunction "T_P$38") (pintype "passive"))
    )
    (net (code "169") (name "unconnected-(P3-U-PadP$39)") (class "Default")
      (node (ref "P3") (pin "P$39") (pinfunction "U_P$39") (pintype "passive"))
    )
    (net (code "170") (name "unconnected-(P3-V-PadP$40)") (class "Default")
      (node (ref "P3") (pin "P$40") (pinfunction "V_P$40") (pintype "passive"))
    )
    (net (code "171") (name "unconnected-(P3-W-PadP$41)") (class "Default")
      (node (ref "P3") (pin "P$41") (pinfunction "W_P$41") (pintype "passive"))
    )
    (net (code "172") (name "unconnected-(P3-X-PadP$42)") (class "Default")
      (node (ref "P3") (pin "P$42") (pinfunction "X_P$42") (pintype "passive"))
    )
    (net (code "173") (name "unconnected-(P3-Y-PadP$43)") (class "Default")
      (node (ref "P3") (pin "P$43") (pinfunction "Y_P$43") (pintype "passive"))
    )
    (net (code "174") (name "unconnected-(P3-Z-PadP$44)") (class "Default")
      (node (ref "P3") (pin "P$44") (pinfunction "Z_P$44") (pintype "passive"))
    )
    (net (code "175") (name "unconnected-(P4-1-PadP$1)") (class "Default")
      (node (ref "P4") (pin "P$1") (pinfunction "1_P$1") (pintype "passive"))
    )
    (net (code "176") (name "unconnected-(P4-2-PadP$2)") (class "Default")
      (node (ref "P4") (pin "P$2") (pinfunction "2_P$2") (pintype "passive"))
    )
    (net (code "177") (name "unconnected-(P4-5-PadP$5)") (class "Default")
      (node (ref "P4") (pin "P$5") (pinfunction "5_P$5") (pintype "passive"))
    )
    (net (code "178") (name "unconnected-(P4-6-PadP$6)") (class "Default")
      (node (ref "P4") (pin "P$6") (pinfunction "6_P$6") (pintype "passive"))
    )
    (net (code "179") (name "unconnected-(P4-7-PadP$7)") (class "Default")
      (node (ref "P4") (pin "P$7") (pinfunction "7_P$7") (pintype "passive"))
    )
    (net (code "180") (name "unconnected-(P4-8-PadP$8)") (class "Default")
      (node (ref "P4") (pin "P$8") (pinfunction "8_P$8") (pintype "passive"))
    )
    (net (code "181") (name "unconnected-(P4-9-PadP$9)") (class "Default")
      (node (ref "P4") (pin "P$9") (pinfunction "9_P$9") (pintype "passive"))
    )
    (net (code "182") (name "unconnected-(P4-10-PadP$10)") (class "Default")
      (node (ref "P4") (pin "P$10") (pinfunction "10_P$10") (pintype "passive"))
    )
    (net (code "183") (name "unconnected-(P4-11-PadP$11)") (class "Default")
      (node (ref "P4") (pin "P$11") (pinfunction "11_P$11") (pintype "passive"))
    )
    (net (code "184") (name "unconnected-(P4-12-PadP$12)") (class "Default")
      (node (ref "P4") (pin "P$12") (pinfunction "12_P$12") (pintype "passive"))
    )
    (net (code "185") (name "unconnected-(P4-13-PadP$13)") (class "Default")
      (node (ref "P4") (pin "P$13") (pinfunction "13_P$13") (pintype "passive"))
    )
    (net (code "186") (name "unconnected-(P4-14-PadP$14)") (class "Default")
      (node (ref "P4") (pin "P$14") (pinfunction "14_P$14") (pintype "passive"))
    )
    (net (code "187") (name "unconnected-(P4-15-PadP$15)") (class "Default")
      (node (ref "P4") (pin "P$15") (pinfunction "15_P$15") (pintype "passive"))
    )
    (net (code "188") (name "unconnected-(P4-16-PadP$16)") (class "Default")
      (node (ref "P4") (pin "P$16") (pinfunction "16_P$16") (pintype "passive"))
    )
    (net (code "189") (name "unconnected-(P4-17-PadP$17)") (class "Default")
      (node (ref "P4") (pin "P$17") (pinfunction "17_P$17") (pintype "passive"))
    )
    (net (code "190") (name "unconnected-(P4-18-PadP$18)") (class "Default")
      (node (ref "P4") (pin "P$18") (pinfunction "18_P$18") (pintype "passive"))
    )
    (net (code "191") (name "unconnected-(P4-19-PadP$19)") (class "Default")
      (node (ref "P4") (pin "P$19") (pinfunction "19_P$19") (pintype "passive"))
    )
    (net (code "192") (name "unconnected-(P4-20-PadP$20)") (class "Default")
      (node (ref "P4") (pin "P$20") (pinfunction "20_P$20") (pintype "passive"))
    )
    (net (code "193") (name "unconnected-(P4-21-PadP$21)") (class "Default")
      (node (ref "P4") (pin "P$21") (pinfunction "21_P$21") (pintype "passive"))
    )
    (net (code "194") (name "unconnected-(P4-22-PadP$22)") (class "Default")
      (node (ref "P4") (pin "P$22") (pinfunction "22_P$22") (pintype "passive"))
    )
    (net (code "195") (name "unconnected-(P4-B-PadP$24)") (class "Default")
      (node (ref "P4") (pin "P$24") (pinfunction "B_P$24") (pintype "passive"))
    )
    (net (code "196") (name "unconnected-(P4-F-PadP$28)") (class "Default")
      (node (ref "P4") (pin "P$28") (pinfunction "F_P$28") (pintype "passive"))
    )
    (net (code "197") (name "unconnected-(P4-J-PadP$30)") (class "Default")
      (node (ref "P4") (pin "P$30") (pinfunction "J_P$30") (pintype "passive"))
    )
    (net (code "198") (name "unconnected-(P4-L-PadP$32)") (class "Default")
      (node (ref "P4") (pin "P$32") (pinfunction "L_P$32") (pintype "passive"))
    )
    (net (code "199") (name "unconnected-(P4-M-PadP$33)") (class "Default")
      (node (ref "P4") (pin "P$33") (pinfunction "M_P$33") (pintype "passive"))
    )
    (net (code "200") (name "unconnected-(P4-N-PadP$34)") (class "Default")
      (node (ref "P4") (pin "P$34") (pinfunction "N_P$34") (pintype "passive"))
    )
    (net (code "201") (name "unconnected-(P4-P-PadP$35)") (class "Default")
      (node (ref "P4") (pin "P$35") (pinfunction "P_P$35") (pintype "passive"))
    )
    (net (code "202") (name "unconnected-(P4-R-PadP$36)") (class "Default")
      (node (ref "P4") (pin "P$36") (pinfunction "R_P$36") (pintype "passive"))
    )
    (net (code "203") (name "unconnected-(P4-S-PadP$37)") (class "Default")
      (node (ref "P4") (pin "P$37") (pinfunction "S_P$37") (pintype "passive"))
    )
    (net (code "204") (name "unconnected-(P4-T-PadP$38)") (class "Default")
      (node (ref "P4") (pin "P$38") (pinfunction "T_P$38") (pintype "passive"))
    )
    (net (code "205") (name "unconnected-(P4-U-PadP$39)") (class "Default")
      (node (ref "P4") (pin "P$39") (pinfunction "U_P$39") (pintype "passive"))
    )
    (net (code "206") (name "unconnected-(P4-V-PadP$40)") (class "Default")
      (node (ref "P4") (pin "P$40") (pinfunction "V_P$40") (pintype "passive"))
    )
    (net (code "207") (name "unconnected-(P4-W-PadP$41)") (class "Default")
      (node (ref "P4") (pin "P$41") (pinfunction "W_P$41") (pintype "passive"))
    )
    (net (code "208") (name "unconnected-(P4-X-PadP$42)") (class "Default")
      (node (ref "P4") (pin "P$42") (pinfunction "X_P$42") (pintype "passive"))
    )
    (net (code "209") (name "unconnected-(P4-Y-PadP$43)") (class "Default")
      (node (ref "P4") (pin "P$43") (pinfunction "Y_P$43") (pintype "passive"))
    )
    (net (code "210") (name "unconnected-(P5-1-PadP$1)") (class "Default")
      (node (ref "P5") (pin "P$1") (pinfunction "1_P$1") (pintype "passive"))
    )
    (net (code "211") (name "unconnected-(P5-2-PadP$2)") (class "Default")
      (node (ref "P5") (pin "P$2") (pinfunction "2_P$2") (pintype "passive"))
    )
    (net (code "212") (name "unconnected-(P5-5-PadP$5)") (class "Default")
      (node (ref "P5") (pin "P$5") (pinfunction "5_P$5") (pintype "passive"))
    )
    (net (code "213") (name "unconnected-(P5-6-PadP$6)") (class "Default")
      (node (ref "P5") (pin "P$6") (pinfunction "6_P$6") (pintype "passive"))
    )
    (net (code "214") (name "unconnected-(P5-7-PadP$7)") (class "Default")
      (node (ref "P5") (pin "P$7") (pinfunction "7_P$7") (pintype "passive"))
    )
    (net (code "215") (name "unconnected-(P5-8-PadP$8)") (class "Default")
      (node (ref "P5") (pin "P$8") (pinfunction "8_P$8") (pintype "passive"))
    )
    (net (code "216") (name "unconnected-(P5-9-PadP$9)") (class "Default")
      (node (ref "P5") (pin "P$9") (pinfunction "9_P$9") (pintype "passive"))
    )
    (net (code "217") (name "unconnected-(P5-10-PadP$10)") (class "Default")
      (node (ref "P5") (pin "P$10") (pinfunction "10_P$10") (pintype "passive"))
    )
    (net (code "218") (name "unconnected-(P5-11-PadP$11)") (class "Default")
      (node (ref "P5") (pin "P$11") (pinfunction "11_P$11") (pintype "passive"))
    )
    (net (code "219") (name "unconnected-(P5-12-PadP$12)") (class "Default")
      (node (ref "P5") (pin "P$12") (pinfunction "12_P$12") (pintype "passive"))
    )
    (net (code "220") (name "unconnected-(P5-13-PadP$13)") (class "Default")
      (node (ref "P5") (pin "P$13") (pinfunction "13_P$13") (pintype "passive"))
    )
    (net (code "221") (name "unconnected-(P5-14-PadP$14)") (class "Default")
      (node (ref "P5") (pin "P$14") (pinfunction "14_P$14") (pintype "passive"))
    )
    (net (code "222") (name "unconnected-(P5-15-PadP$15)") (class "Default")
      (node (ref "P5") (pin "P$15") (pinfunction "15_P$15") (pintype "passive"))
    )
    (net (code "223") (name "unconnected-(P5-16-PadP$16)") (class "Default")
      (node (ref "P5") (pin "P$16") (pinfunction "16_P$16") (pintype "passive"))
    )
    (net (code "224") (name "unconnected-(P5-17-PadP$17)") (class "Default")
      (node (ref "P5") (pin "P$17") (pinfunction "17_P$17") (pintype "passive"))
    )
    (net (code "225") (name "unconnected-(P5-18-PadP$18)") (class "Default")
      (node (ref "P5") (pin "P$18") (pinfunction "18_P$18") (pintype "passive"))
    )
    (net (code "226") (name "unconnected-(P5-19-PadP$19)") (class "Default")
      (node (ref "P5") (pin "P$19") (pinfunction "19_P$19") (pintype "passive"))
    )
    (net (code "227") (name "unconnected-(P5-20-PadP$20)") (class "Default")
      (node (ref "P5") (pin "P$20") (pinfunction "20_P$20") (pintype "passive"))
    )
    (net (code "228") (name "unconnected-(P5-21-PadP$21)") (class "Default")
      (node (ref "P5") (pin "P$21") (pinfunction "21_P$21") (pintype "passive"))
    )
    (net (code "229") (name "unconnected-(P5-22-PadP$22)") (class "Default")
      (node (ref "P5") (pin "P$22") (pinfunction "22_P$22") (pintype "passive"))
    )
    (net (code "230") (name "unconnected-(P5-B-PadP$24)") (class "Default")
      (node (ref "P5") (pin "P$24") (pinfunction "B_P$24") (pintype "passive"))
    )
    (net (code "231") (name "unconnected-(P5-F-PadP$28)") (class "Default")
      (node (ref "P5") (pin "P$28") (pinfunction "F_P$28") (pintype "passive"))
    )
    (net (code "232") (name "unconnected-(P5-J-PadP$30)") (class "Default")
      (node (ref "P5") (pin "P$30") (pinfunction "J_P$30") (pintype "passive"))
    )
    (net (code "233") (name "unconnected-(P5-L-PadP$32)") (class "Default")
      (node (ref "P5") (pin "P$32") (pinfunction "L_P$32") (pintype "passive"))
    )
    (net (code "234") (name "unconnected-(P5-M-PadP$33)") (class "Default")
      (node (ref "P5") (pin "P$33") (pinfunction "M_P$33") (pintype "passive"))
    )
    (net (code "235") (name "unconnected-(P5-N-PadP$34)") (class "Default")
      (node (ref "P5") (pin "P$34") (pinfunction "N_P$34") (pintype "passive"))
    )
    (net (code "236") (name "unconnected-(P5-P-PadP$35)") (class "Default")
      (node (ref "P5") (pin "P$35") (pinfunction "P_P$35") (pintype "passive"))
    )
    (net (code "237") (name "unconnected-(P5-R-PadP$36)") (class "Default")
      (node (ref "P5") (pin "P$36") (pinfunction "R_P$36") (pintype "passive"))
    )
    (net (code "238") (name "unconnected-(P5-S-PadP$37)") (class "Default")
      (node (ref "P5") (pin "P$37") (pinfunction "S_P$37") (pintype "passive"))
    )
    (net (code "239") (name "unconnected-(P5-T-PadP$38)") (class "Default")
      (node (ref "P5") (pin "P$38") (pinfunction "T_P$38") (pintype "passive"))
    )
    (net (code "240") (name "unconnected-(P5-U-PadP$39)") (class "Default")
      (node (ref "P5") (pin "P$39") (pinfunction "U_P$39") (pintype "passive"))
    )
    (net (code "241") (name "unconnected-(P5-V-PadP$40)") (class "Default")
      (node (ref "P5") (pin "P$40") (pinfunction "V_P$40") (pintype "passive"))
    )
    (net (code "242") (name "unconnected-(P5-W-PadP$41)") (class "Default")
      (node (ref "P5") (pin "P$41") (pinfunction "W_P$41") (pintype "passive"))
    )
    (net (code "243") (name "unconnected-(P5-X-PadP$42)") (class "Default")
      (node (ref "P5") (pin "P$42") (pinfunction "X_P$42") (pintype "passive"))
    )
    (net (code "244") (name "unconnected-(P5-Y-PadP$43)") (class "Default")
      (node (ref "P5") (pin "P$43") (pinfunction "Y_P$43") (pintype "passive"))
    )
    (net (code "245") (name "unconnected-(P6-1-PadP$1)") (class "Default")
      (node (ref "P6") (pin "P$1") (pinfunction "1_P$1") (pintype "passive"))
    )
    (net (code "246") (name "unconnected-(P6-2-PadP$2)") (class "Default")
      (node (ref "P6") (pin "P$2") (pinfunction "2_P$2") (pintype "passive"))
    )
    (net (code "247") (name "unconnected-(P6-3-PadP$3)") (class "Default")
      (node (ref "P6") (pin "P$3") (pinfunction "3_P$3") (pintype "passive"))
    )
    (net (code "248") (name "unconnected-(P6-5-PadP$5)") (class "Default")
      (node (ref "P6") (pin "P$5") (pinfunction "5_P$5") (pintype "passive"))
    )
    (net (code "249") (name "unconnected-(P6-6-PadP$6)") (class "Default")
      (node (ref "P6") (pin "P$6") (pinfunction "6_P$6") (pintype "passive"))
    )
    (net (code "250") (name "unconnected-(P6-7-PadP$7)") (class "Default")
      (node (ref "P6") (pin "P$7") (pinfunction "7_P$7") (pintype "passive"))
    )
    (net (code "251") (name "unconnected-(P6-8-PadP$8)") (class "Default")
      (node (ref "P6") (pin "P$8") (pinfunction "8_P$8") (pintype "passive"))
    )
    (net (code "252") (name "unconnected-(P6-9-PadP$9)") (class "Default")
      (node (ref "P6") (pin "P$9") (pinfunction "9_P$9") (pintype "passive"))
    )
    (net (code "253") (name "unconnected-(P6-10-PadP$10)") (class "Default")
      (node (ref "P6") (pin "P$10") (pinfunction "10_P$10") (pintype "passive"))
    )
    (net (code "254") (name "unconnected-(P6-11-PadP$11)") (class "Default")
      (node (ref "P6") (pin "P$11") (pinfunction "11_P$11") (pintype "passive"))
    )
    (net (code "255") (name "unconnected-(P6-12-PadP$12)") (class "Default")
      (node (ref "P6") (pin "P$12") (pinfunction "12_P$12") (pintype "passive"))
    )
    (net (code "256") (name "unconnected-(P6-13-PadP$13)") (class "Default")
      (node (ref "P6") (pin "P$13") (pinfunction "13_P$13") (pintype "passive"))
    )
    (net (code "257") (name "unconnected-(P6-14-PadP$14)") (class "Default")
      (node (ref "P6") (pin "P$14") (pinfunction "14_P$14") (pintype "passive"))
    )
    (net (code "258") (name "unconnected-(P6-15-PadP$15)") (class "Default")
      (node (ref "P6") (pin "P$15") (pinfunction "15_P$15") (pintype "passive"))
    )
    (net (code "259") (name "unconnected-(P6-16-PadP$16)") (class "Default")
      (node (ref "P6") (pin "P$16") (pinfunction "16_P$16") (pintype "passive"))
    )
    (net (code "260") (name "unconnected-(P6-17-PadP$17)") (class "Default")
      (node (ref "P6") (pin "P$17") (pinfunction "17_P$17") (pintype "passive"))
    )
    (net (code "261") (name "unconnected-(P6-18-PadP$18)") (class "Default")
      (node (ref "P6") (pin "P$18") (pinfunction "18_P$18") (pintype "passive"))
    )
    (net (code "262") (name "unconnected-(P6-19-PadP$19)") (class "Default")
      (node (ref "P6") (pin "P$19") (pinfunction "19_P$19") (pintype "passive"))
    )
    (net (code "263") (name "unconnected-(P6-20-PadP$20)") (class "Default")
      (node (ref "P6") (pin "P$20") (pinfunction "20_P$20") (pintype "passive"))
    )
    (net (code "264") (name "unconnected-(P6-21-PadP$21)") (class "Default")
      (node (ref "P6") (pin "P$21") (pinfunction "21_P$21") (pintype "passive"))
    )
    (net (code "265") (name "unconnected-(P6-22-PadP$22)") (class "Default")
      (node (ref "P6") (pin "P$22") (pinfunction "22_P$22") (pintype "passive"))
    )
    (net (code "266") (name "unconnected-(P6-A-PadP$23)") (class "Default")
      (node (ref "P6") (pin "P$23") (pinfunction "A_P$23") (pintype "passive"))
    )
    (net (code "267") (name "unconnected-(P6-B-PadP$24)") (class "Default")
      (node (ref "P6") (pin "P$24") (pinfunction "B_P$24") (pintype "passive"))
    )
    (net (code "268") (name "unconnected-(P6-C-PadP$25)") (class "Default")
      (node (ref "P6") (pin "P$25") (pinfunction "C_P$25") (pintype "passive"))
    )
    (net (code "269") (name "unconnected-(P6-F-PadP$28)") (class "Default")
      (node (ref "P6") (pin "P$28") (pinfunction "F_P$28") (pintype "passive"))
    )
    (net (code "270") (name "unconnected-(P6-H-PadP$29)") (class "Default")
      (node (ref "P6") (pin "P$29") (pinfunction "H_P$29") (pintype "passive"))
    )
    (net (code "271") (name "unconnected-(P6-J-PadP$30)") (class "Default")
      (node (ref "P6") (pin "P$30") (pinfunction "J_P$30") (pintype "passive"))
    )
    (net (code "272") (name "unconnected-(P6-K-PadP$31)") (class "Default")
      (node (ref "P6") (pin "P$31") (pinfunction "K_P$31") (pintype "passive"))
    )
    (net (code "273") (name "unconnected-(P6-L-PadP$32)") (class "Default")
      (node (ref "P6") (pin "P$32") (pinfunction "L_P$32") (pintype "passive"))
    )
    (net (code "274") (name "unconnected-(P6-N-PadP$34)") (class "Default")
      (node (ref "P6") (pin "P$34") (pinfunction "N_P$34") (pintype "passive"))
    )
    (net (code "275") (name "unconnected-(P6-P-PadP$35)") (class "Default")
      (node (ref "P6") (pin "P$35") (pinfunction "P_P$35") (pintype "passive"))
    )
    (net (code "276") (name "unconnected-(P6-R-PadP$36)") (class "Default")
      (node (ref "P6") (pin "P$36") (pinfunction "R_P$36") (pintype "passive"))
    )
    (net (code "277") (name "unconnected-(P6-S-PadP$37)") (class "Default")
      (node (ref "P6") (pin "P$37") (pinfunction "S_P$37") (pintype "passive"))
    )
    (net (code "278") (name "unconnected-(P6-T-PadP$38)") (class "Default")
      (node (ref "P6") (pin "P$38") (pinfunction "T_P$38") (pintype "passive"))
    )
    (net (code "279") (name "unconnected-(P6-U-PadP$39)") (class "Default")
      (node (ref "P6") (pin "P$39") (pinfunction "U_P$39") (pintype "passive"))
    )
    (net (code "280") (name "unconnected-(P6-V-PadP$40)") (class "Default")
      (node (ref "P6") (pin "P$40") (pinfunction "V_P$40") (pintype "passive"))
    )
    (net (code "281") (name "unconnected-(P6-X-PadP$42)") (class "Default")
      (node (ref "P6") (pin "P$42") (pinfunction "X_P$42") (pintype "passive"))
    )
    (net (code "282") (name "unconnected-(P6-Y-PadP$43)") (class "Default")
      (node (ref "P6") (pin "P$43") (pinfunction "Y_P$43") (pintype "passive"))
    )
    (net (code "283") (name "unconnected-(P7-1-PadP$1)") (class "Default")
      (node (ref "P7") (pin "P$1") (pinfunction "1_P$1") (pintype "passive"))
    )
    (net (code "284") (name "unconnected-(P7-2-PadP$2)") (class "Default")
      (node (ref "P7") (pin "P$2") (pinfunction "2_P$2") (pintype "passive"))
    )
    (net (code "285") (name "unconnected-(P7-3-PadP$3)") (class "Default")
      (node (ref "P7") (pin "P$3") (pinfunction "3_P$3") (pintype "passive"))
    )
    (net (code "286") (name "unconnected-(P7-5-PadP$5)") (class "Default")
      (node (ref "P7") (pin "P$5") (pinfunction "5_P$5") (pintype "passive"))
    )
    (net (code "287") (name "unconnected-(P7-6-PadP$6)") (class "Default")
      (node (ref "P7") (pin "P$6") (pinfunction "6_P$6") (pintype "passive"))
    )
    (net (code "288") (name "unconnected-(P7-7-PadP$7)") (class "Default")
      (node (ref "P7") (pin "P$7") (pinfunction "7_P$7") (pintype "passive"))
    )
    (net (code "289") (name "unconnected-(P7-8-PadP$8)") (class "Default")
      (node (ref "P7") (pin "P$8") (pinfunction "8_P$8") (pintype "passive"))
    )
    (net (code "290") (name "unconnected-(P7-9-PadP$9)") (class "Default")
      (node (ref "P7") (pin "P$9") (pinfunction "9_P$9") (pintype "passive"))
    )
    (net (code "291") (name "unconnected-(P7-10-PadP$10)") (class "Default")
      (node (ref "P7") (pin "P$10") (pinfunction "10_P$10") (pintype "passive"))
    )
    (net (code "292") (name "unconnected-(P7-11-PadP$11)") (class "Default")
      (node (ref "P7") (pin "P$11") (pinfunction "11_P$11") (pintype "passive"))
    )
    (net (code "293") (name "unconnected-(P7-12-PadP$12)") (class "Default")
      (node (ref "P7") (pin "P$12") (pinfunction "12_P$12") (pintype "passive"))
    )
    (net (code "294") (name "unconnected-(P7-13-PadP$13)") (class "Default")
      (node (ref "P7") (pin "P$13") (pinfunction "13_P$13") (pintype "passive"))
    )
    (net (code "295") (name "unconnected-(P7-14-PadP$14)") (class "Default")
      (node (ref "P7") (pin "P$14") (pinfunction "14_P$14") (pintype "passive"))
    )
    (net (code "296") (name "unconnected-(P7-15-PadP$15)") (class "Default")
      (node (ref "P7") (pin "P$15") (pinfunction "15_P$15") (pintype "passive"))
    )
    (net (code "297") (name "unconnected-(P7-16-PadP$16)") (class "Default")
      (node (ref "P7") (pin "P$16") (pinfunction "16_P$16") (pintype "passive"))
    )
    (net (code "298") (name "unconnected-(P7-17-PadP$17)") (class "Default")
      (node (ref "P7") (pin "P$17") (pinfunction "17_P$17") (pintype "passive"))
    )
    (net (code "299") (name "unconnected-(P7-18-PadP$18)") (class "Default")
      (node (ref "P7") (pin "P$18") (pinfunction "18_P$18") (pintype "passive"))
    )
    (net (code "300") (name "unconnected-(P7-19-PadP$19)") (class "Default")
      (node (ref "P7") (pin "P$19") (pinfunction "19_P$19") (pintype "passive"))
    )
    (net (code "301") (name "unconnected-(P7-20-PadP$20)") (class "Default")
      (node (ref "P7") (pin "P$20") (pinfunction "20_P$20") (pintype "passive"))
    )
    (net (code "302") (name "unconnected-(P7-21-PadP$21)") (class "Default")
      (node (ref "P7") (pin "P$21") (pinfunction "21_P$21") (pintype "passive"))
    )
    (net (code "303") (name "unconnected-(P7-22-PadP$22)") (class "Default")
      (node (ref "P7") (pin "P$22") (pinfunction "22_P$22") (pintype "passive"))
    )
    (net (code "304") (name "unconnected-(P7-A-PadP$23)") (class "Default")
      (node (ref "P7") (pin "P$23") (pinfunction "A_P$23") (pintype "passive"))
    )
    (net (code "305") (name "unconnected-(P7-B-PadP$24)") (class "Default")
      (node (ref "P7") (pin "P$24") (pinfunction "B_P$24") (pintype "passive"))
    )
    (net (code "306") (name "unconnected-(P7-C-PadP$25)") (class "Default")
      (node (ref "P7") (pin "P$25") (pinfunction "C_P$25") (pintype "passive"))
    )
    (net (code "307") (name "unconnected-(P7-F-PadP$28)") (class "Default")
      (node (ref "P7") (pin "P$28") (pinfunction "F_P$28") (pintype "passive"))
    )
    (net (code "308") (name "unconnected-(P7-H-PadP$29)") (class "Default")
      (node (ref "P7") (pin "P$29") (pinfunction "H_P$29") (pintype "passive"))
    )
    (net (code "309") (name "unconnected-(P7-J-PadP$30)") (class "Default")
      (node (ref "P7") (pin "P$30") (pinfunction "J_P$30") (pintype "passive"))
    )
    (net (code "310") (name "unconnected-(P7-K-PadP$31)") (class "Default")
      (node (ref "P7") (pin "P$31") (pinfunction "K_P$31") (pintype "passive"))
    )
    (net (code "311") (name "unconnected-(P7-L-PadP$32)") (class "Default")
      (node (ref "P7") (pin "P$32") (pinfunction "L_P$32") (pintype "passive"))
    )
    (net (code "312") (name "unconnected-(P7-N-PadP$34)") (class "Default")
      (node (ref "P7") (pin "P$34") (pinfunction "N_P$34") (pintype "passive"))
    )
    (net (code "313") (name "unconnected-(P7-P-PadP$35)") (class "Default")
      (node (ref "P7") (pin "P$35") (pinfunction "P_P$35") (pintype "passive"))
    )
    (net (code "314") (name "unconnected-(P7-R-PadP$36)") (class "Default")
      (node (ref "P7") (pin "P$36") (pinfunction "R_P$36") (pintype "passive"))
    )
    (net (code "315") (name "unconnected-(P7-S-PadP$37)") (class "Default")
      (node (ref "P7") (pin "P$37") (pinfunction "S_P$37") (pintype "passive"))
    )
    (net (code "316") (name "unconnected-(P7-T-PadP$38)") (class "Default")
      (node (ref "P7") (pin "P$38") (pinfunction "T_P$38") (pintype "passive"))
    )
    (net (code "317") (name "unconnected-(P7-U-PadP$39)") (class "Default")
      (node (ref "P7") (pin "P$39") (pinfunction "U_P$39") (pintype "passive"))
    )
    (net (code "318") (name "unconnected-(P7-V-PadP$40)") (class "Default")
      (node (ref "P7") (pin "P$40") (pinfunction "V_P$40") (pintype "passive"))
    )
    (net (code "319") (name "unconnected-(P7-X-PadP$42)") (class "Default")
      (node (ref "P7") (pin "P$42") (pinfunction "X_P$42") (pintype "passive"))
    )
    (net (code "320") (name "unconnected-(P7-Y-PadP$43)") (class "Default")
      (node (ref "P7") (pin "P$43") (pinfunction "Y_P$43") (pintype "passive"))
    )
    (net (code "321") (name "unconnected-(P8-1-PadP$1)") (class "Default")
      (node (ref "P8") (pin "P$1") (pinfunction "1_P$1") (pintype "passive"))
    )
    (net (code "322") (name "unconnected-(P8-2-PadP$2)") (class "Default")
      (node (ref "P8") (pin "P$2") (pinfunction "2_P$2") (pintype "passive"))
    )
    (net (code "323") (name "unconnected-(P8-3-PadP$3)") (class "Default")
      (node (ref "P8") (pin "P$3") (pinfunction "3_P$3") (pintype "passive"))
    )
    (net (code "324") (name "unconnected-(P8-4-PadP$4)") (class "Default")
      (node (ref "P8") (pin "P$4") (pinfunction "4_P$4") (pintype "passive"))
    )
    (net (code "325") (name "unconnected-(P8-5-PadP$5)") (class "Default")
      (node (ref "P8") (pin "P$5") (pinfunction "5_P$5") (pintype "passive"))
    )
    (net (code "326") (name "unconnected-(P8-6-PadP$6)") (class "Default")
      (node (ref "P8") (pin "P$6") (pinfunction "6_P$6") (pintype "passive"))
    )
    (net (code "327") (name "unconnected-(P8-7-PadP$7)") (class "Default")
      (node (ref "P8") (pin "P$7") (pinfunction "7_P$7") (pintype "passive"))
    )
    (net (code "328") (name "unconnected-(P8-8-PadP$8)") (class "Default")
      (node (ref "P8") (pin "P$8") (pinfunction "8_P$8") (pintype "passive"))
    )
    (net (code "329") (name "unconnected-(P8-9-PadP$9)") (class "Default")
      (node (ref "P8") (pin "P$9") (pinfunction "9_P$9") (pintype "passive"))
    )
    (net (code "330") (name "unconnected-(P8-10-PadP$10)") (class "Default")
      (node (ref "P8") (pin "P$10") (pinfunction "10_P$10") (pintype "passive"))
    )
    (net (code "331") (name "unconnected-(P8-11-PadP$11)") (class "Default")
      (node (ref "P8") (pin "P$11") (pinfunction "11_P$11") (pintype "passive"))
    )
    (net (code "332") (name "unconnected-(P8-12-PadP$12)") (class "Default")
      (node (ref "P8") (pin "P$12") (pinfunction "12_P$12") (pintype "passive"))
    )
    (net (code "333") (name "unconnected-(P8-13-PadP$13)") (class "Default")
      (node (ref "P8") (pin "P$13") (pinfunction "13_P$13") (pintype "passive"))
    )
    (net (code "334") (name "unconnected-(P8-14-PadP$14)") (class "Default")
      (node (ref "P8") (pin "P$14") (pinfunction "14_P$14") (pintype "passive"))
    )
    (net (code "335") (name "unconnected-(P8-15-PadP$15)") (class "Default")
      (node (ref "P8") (pin "P$15") (pinfunction "15_P$15") (pintype "passive"))
    )
    (net (code "336") (name "unconnected-(P8-16-PadP$16)") (class "Default")
      (node (ref "P8") (pin "P$16") (pinfunction "16_P$16") (pintype "passive"))
    )
    (net (code "337") (name "unconnected-(P8-17-PadP$17)") (class "Default")
      (node (ref "P8") (pin "P$17") (pinfunction "17_P$17") (pintype "passive"))
    )
    (net (code "338") (name "unconnected-(P8-18-PadP$18)") (class "Default")
      (node (ref "P8") (pin "P$18") (pinfunction "18_P$18") (pintype "passive"))
    )
    (net (code "339") (name "unconnected-(P8-19-PadP$19)") (class "Default")
      (node (ref "P8") (pin "P$19") (pinfunction "19_P$19") (pintype "passive"))
    )
    (net (code "340") (name "unconnected-(P8-20-PadP$20)") (class "Default")
      (node (ref "P8") (pin "P$20") (pinfunction "20_P$20") (pintype "passive"))
    )
    (net (code "341") (name "unconnected-(P8-21-PadP$21)") (class "Default")
      (node (ref "P8") (pin "P$21") (pinfunction "21_P$21") (pintype "passive"))
    )
    (net (code "342") (name "unconnected-(P8-22-PadP$22)") (class "Default")
      (node (ref "P8") (pin "P$22") (pinfunction "22_P$22") (pintype "passive"))
    )
    (net (code "343") (name "unconnected-(P8-A-PadP$23)") (class "Default")
      (node (ref "P8") (pin "P$23") (pinfunction "A_P$23") (pintype "passive"))
    )
    (net (code "344") (name "unconnected-(P8-B-PadP$24)") (class "Default")
      (node (ref "P8") (pin "P$24") (pinfunction "B_P$24") (pintype "passive"))
    )
    (net (code "345") (name "unconnected-(P8-C-PadP$25)") (class "Default")
      (node (ref "P8") (pin "P$25") (pinfunction "C_P$25") (pintype "passive"))
    )
    (net (code "346") (name "unconnected-(P8-D-PadP$26)") (class "Default")
      (node (ref "P8") (pin "P$26") (pinfunction "D_P$26") (pintype "passive"))
    )
    (net (code "347") (name "unconnected-(P8-E-PadP$27)") (class "Default")
      (node (ref "P8") (pin "P$27") (pinfunction "E_P$27") (pintype "passive"))
    )
    (net (code "348") (name "unconnected-(P8-F-PadP$28)") (class "Default")
      (node (ref "P8") (pin "P$28") (pinfunction "F_P$28") (pintype "passive"))
    )
    (net (code "349") (name "unconnected-(P8-H-PadP$29)") (class "Default")
      (node (ref "P8") (pin "P$29") (pinfunction "H_P$29") (pintype "passive"))
    )
    (net (code "350") (name "unconnected-(P8-J-PadP$30)") (class "Default")
      (node (ref "P8") (pin "P$30") (pinfunction "J_P$30") (pintype "passive"))
    )
    (net (code "351") (name "unconnected-(P8-K-PadP$31)") (class "Default")
      (node (ref "P8") (pin "P$31") (pinfunction "K_P$31") (pintype "passive"))
    )
    (net (code "352") (name "unconnected-(P8-L-PadP$32)") (class "Default")
      (node (ref "P8") (pin "P$32") (pinfunction "L_P$32") (pintype "passive"))
    )
    (net (code "353") (name "unconnected-(P8-M-PadP$33)") (class "Default")
      (node (ref "P8") (pin "P$33") (pinfunction "M_P$33") (pintype "passive"))
    )
    (net (code "354") (name "unconnected-(P8-N-PadP$34)") (class "Default")
      (node (ref "P8") (pin "P$34") (pinfunction "N_P$34") (pintype "passive"))
    )
    (net (code "355") (name "unconnected-(P8-P-PadP$35)") (class "Default")
      (node (ref "P8") (pin "P$35") (pinfunction "P_P$35") (pintype "passive"))
    )
    (net (code "356") (name "unconnected-(P8-R-PadP$36)") (class "Default")
      (node (ref "P8") (pin "P$36") (pinfunction "R_P$36") (pintype "passive"))
    )
    (net (code "357") (name "unconnected-(P8-S-PadP$37)") (class "Default")
      (node (ref "P8") (pin "P$37") (pinfunction "S_P$37") (pintype "passive"))
    )
    (net (code "358") (name "unconnected-(P8-T-PadP$38)") (class "Default")
      (node (ref "P8") (pin "P$38") (pinfunction "T_P$38") (pintype "passive"))
    )
    (net (code "359") (name "unconnected-(P8-U-PadP$39)") (class "Default")
      (node (ref "P8") (pin "P$39") (pinfunction "U_P$39") (pintype "passive"))
    )
    (net (code "360") (name "unconnected-(P8-V-PadP$40)") (class "Default")
      (node (ref "P8") (pin "P$40") (pinfunction "V_P$40") (pintype "passive"))
    )
    (net (code "361") (name "unconnected-(P8-W-PadP$41)") (class "Default")
      (node (ref "P8") (pin "P$41") (pinfunction "W_P$41") (pintype "passive"))
    )
    (net (code "362") (name "unconnected-(P8-X-PadP$42)") (class "Default")
      (node (ref "P8") (pin "P$42") (pinfunction "X_P$42") (pintype "passive"))
    )
    (net (code "363") (name "unconnected-(P8-Y-PadP$43)") (class "Default")
      (node (ref "P8") (pin "P$43") (pinfunction "Y_P$43") (pintype "passive"))
    )
    (net (code "364") (name "unconnected-(P8-Z-PadP$44)") (class "Default")
      (node (ref "P8") (pin "P$44") (pinfunction "Z_P$44") (pintype "passive"))
    )
    (net (code "365") (name "unconnected-(P9-1-PadP$1)") (class "Default")
      (node (ref "P9") (pin "P$1") (pinfunction "1_P$1") (pintype "passive"))
    )
    (net (code "366") (name "unconnected-(P9-2-PadP$2)") (class "Default")
      (node (ref "P9") (pin "P$2") (pinfunction "2_P$2") (pintype "passive"))
    )
    (net (code "367") (name "unconnected-(P9-3-PadP$3)") (class "Default")
      (node (ref "P9") (pin "P$3") (pinfunction "3_P$3") (pintype "passive"))
    )
    (net (code "368") (name "unconnected-(P9-4-PadP$4)") (class "Default")
      (node (ref "P9") (pin "P$4") (pinfunction "4_P$4") (pintype "passive"))
    )
    (net (code "369") (name "unconnected-(P9-5-PadP$5)") (class "Default")
      (node (ref "P9") (pin "P$5") (pinfunction "5_P$5") (pintype "passive"))
    )
    (net (code "370") (name "unconnected-(P9-6-PadP$6)") (class "Default")
      (node (ref "P9") (pin "P$6") (pinfunction "6_P$6") (pintype "passive"))
    )
    (net (code "371") (name "unconnected-(P9-7-PadP$7)") (class "Default")
      (node (ref "P9") (pin "P$7") (pinfunction "7_P$7") (pintype "passive"))
    )
    (net (code "372") (name "unconnected-(P9-8-PadP$8)") (class "Default")
      (node (ref "P9") (pin "P$8") (pinfunction "8_P$8") (pintype "passive"))
    )
    (net (code "373") (name "unconnected-(P9-9-PadP$9)") (class "Default")
      (node (ref "P9") (pin "P$9") (pinfunction "9_P$9") (pintype "passive"))
    )
    (net (code "374") (name "unconnected-(P9-10-PadP$10)") (class "Default")
      (node (ref "P9") (pin "P$10") (pinfunction "10_P$10") (pintype "passive"))
    )
    (net (code "375") (name "unconnected-(P9-11-PadP$11)") (class "Default")
      (node (ref "P9") (pin "P$11") (pinfunction "11_P$11") (pintype "passive"))
    )
    (net (code "376") (name "unconnected-(P9-12-PadP$12)") (class "Default")
      (node (ref "P9") (pin "P$12") (pinfunction "12_P$12") (pintype "passive"))
    )
    (net (code "377") (name "unconnected-(P9-13-PadP$13)") (class "Default")
      (node (ref "P9") (pin "P$13") (pinfunction "13_P$13") (pintype "passive"))
    )
    (net (code "378") (name "unconnected-(P9-14-PadP$14)") (class "Default")
      (node (ref "P9") (pin "P$14") (pinfunction "14_P$14") (pintype "passive"))
    )
    (net (code "379") (name "unconnected-(P9-15-PadP$15)") (class "Default")
      (node (ref "P9") (pin "P$15") (pinfunction "15_P$15") (pintype "passive"))
    )
    (net (code "380") (name "unconnected-(P9-16-PadP$16)") (class "Default")
      (node (ref "P9") (pin "P$16") (pinfunction "16_P$16") (pintype "passive"))
    )
    (net (code "381") (name "unconnected-(P9-17-PadP$17)") (class "Default")
      (node (ref "P9") (pin "P$17") (pinfunction "17_P$17") (pintype "passive"))
    )
    (net (code "382") (name "unconnected-(P9-18-PadP$18)") (class "Default")
      (node (ref "P9") (pin "P$18") (pinfunction "18_P$18") (pintype "passive"))
    )
    (net (code "383") (name "unconnected-(P9-19-PadP$19)") (class "Default")
      (node (ref "P9") (pin "P$19") (pinfunction "19_P$19") (pintype "passive"))
    )
    (net (code "384") (name "unconnected-(P9-20-PadP$20)") (class "Default")
      (node (ref "P9") (pin "P$20") (pinfunction "20_P$20") (pintype "passive"))
    )
    (net (code "385") (name "unconnected-(P9-21-PadP$21)") (class "Default")
      (node (ref "P9") (pin "P$21") (pinfunction "21_P$21") (pintype "passive"))
    )
    (net (code "386") (name "unconnected-(P9-22-PadP$22)") (class "Default")
      (node (ref "P9") (pin "P$22") (pinfunction "22_P$22") (pintype "passive"))
    )
    (net (code "387") (name "unconnected-(P9-A-PadP$23)") (class "Default")
      (node (ref "P9") (pin "P$23") (pinfunction "A_P$23") (pintype "passive"))
    )
    (net (code "388") (name "unconnected-(P9-B-PadP$24)") (class "Default")
      (node (ref "P9") (pin "P$24") (pinfunction "B_P$24") (pintype "passive"))
    )
    (net (code "389") (name "unconnected-(P9-C-PadP$25)") (class "Default")
      (node (ref "P9") (pin "P$25") (pinfunction "C_P$25") (pintype "passive"))
    )
    (net (code "390") (name "unconnected-(P9-D-PadP$26)") (class "Default")
      (node (ref "P9") (pin "P$26") (pinfunction "D_P$26") (pintype "passive"))
    )
    (net (code "391") (name "unconnected-(P9-E-PadP$27)") (class "Default")
      (node (ref "P9") (pin "P$27") (pinfunction "E_P$27") (pintype "passive"))
    )
    (net (code "392") (name "unconnected-(P9-F-PadP$28)") (class "Default")
      (node (ref "P9") (pin "P$28") (pinfunction "F_P$28") (pintype "passive"))
    )
    (net (code "393") (name "unconnected-(P9-H-PadP$29)") (class "Default")
      (node (ref "P9") (pin "P$29") (pinfunction "H_P$29") (pintype "passive"))
    )
    (net (code "394") (name "unconnected-(P9-J-PadP$30)") (class "Default")
      (node (ref "P9") (pin "P$30") (pinfunction "J_P$30") (pintype "passive"))
    )
    (net (code "395") (name "unconnected-(P9-K-PadP$31)") (class "Default")
      (node (ref "P9") (pin "P$31") (pinfunction "K_P$31") (pintype "passive"))
    )
    (net (code "396") (name "unconnected-(P9-L-PadP$32)") (class "Default")
      (node (ref "P9") (pin "P$32") (pinfunction "L_P$32") (pintype "passive"))
    )
    (net (code "397") (name "unconnected-(P9-M-PadP$33)") (class "Default")
      (node (ref "P9") (pin "P$33") (pinfunction "M_P$33") (pintype "passive"))
    )
    (net (code "398") (name "unconnected-(P9-N-PadP$34)") (class "Default")
      (node (ref "P9") (pin "P$34") (pinfunction "N_P$34") (pintype "passive"))
    )
    (net (code "399") (name "unconnected-(P9-P-PadP$35)") (class "Default")
      (node (ref "P9") (pin "P$35") (pinfunction "P_P$35") (pintype "passive"))
    )
    (net (code "400") (name "unconnected-(P9-R-PadP$36)") (class "Default")
      (node (ref "P9") (pin "P$36") (pinfunction "R_P$36") (pintype "passive"))
    )
    (net (code "401") (name "unconnected-(P9-S-PadP$37)") (class "Default")
      (node (ref "P9") (pin "P$37") (pinfunction "S_P$37") (pintype "passive"))
    )
    (net (code "402") (name "unconnected-(P9-T-PadP$38)") (class "Default")
      (node (ref "P9") (pin "P$38") (pinfunction "T_P$38") (pintype "passive"))
    )
    (net (code "403") (name "unconnected-(P9-U-PadP$39)") (class "Default")
      (node (ref "P9") (pin "P$39") (pinfunction "U_P$39") (pintype "passive"))
    )
    (net (code "404") (name "unconnected-(P9-V-PadP$40)") (class "Default")
      (node (ref "P9") (pin "P$40") (pinfunction "V_P$40") (pintype "passive"))
    )
    (net (code "405") (name "unconnected-(P9-W-PadP$41)") (class "Default")
      (node (ref "P9") (pin "P$41") (pinfunction "W_P$41") (pintype "passive"))
    )
    (net (code "406") (name "unconnected-(P9-X-PadP$42)") (class "Default")
      (node (ref "P9") (pin "P$42") (pinfunction "X_P$42") (pintype "passive"))
    )
    (net (code "407") (name "unconnected-(P9-Y-PadP$43)") (class "Default")
      (node (ref "P9") (pin "P$43") (pinfunction "Y_P$43") (pintype "passive"))
    )
    (net (code "408") (name "unconnected-(P9-Z-PadP$44)") (class "Default")
      (node (ref "P9") (pin "P$44") (pinfunction "Z_P$44") (pintype "passive"))
    )
    (net (code "409") (name "unconnected-(P11-1-PadP$1)") (class "Default")
      (node (ref "P11") (pin "P$1") (pinfunction "1_P$1") (pintype "passive"))
    )
    (net (code "410") (name "unconnected-(P11-2-PadP$2)") (class "Default")
      (node (ref "P11") (pin "P$2") (pinfunction "2_P$2") (pintype "passive"))
    )
    (net (code "411") (name "unconnected-(P11-3-PadP$3)") (class "Default")
      (node (ref "P11") (pin "P$3") (pinfunction "3_P$3") (pintype "passive"))
    )
    (net (code "412") (name "unconnected-(P11-5-PadP$5)") (class "Default")
      (node (ref "P11") (pin "P$5") (pinfunction "5_P$5") (pintype "passive"))
    )
    (net (code "413") (name "unconnected-(P11-6-PadP$6)") (class "Default")
      (node (ref "P11") (pin "P$6") (pinfunction "6_P$6") (pintype "passive"))
    )
    (net (code "414") (name "unconnected-(P11-7-PadP$7)") (class "Default")
      (node (ref "P11") (pin "P$7") (pinfunction "7_P$7") (pintype "passive"))
    )
    (net (code "415") (name "unconnected-(P11-8-PadP$8)") (class "Default")
      (node (ref "P11") (pin "P$8") (pinfunction "8_P$8") (pintype "passive"))
    )
    (net (code "416") (name "unconnected-(P11-9-PadP$9)") (class "Default")
      (node (ref "P11") (pin "P$9") (pinfunction "9_P$9") (pintype "passive"))
    )
    (net (code "417") (name "unconnected-(P11-10-PadP$10)") (class "Default")
      (node (ref "P11") (pin "P$10") (pinfunction "10_P$10") (pintype "passive"))
    )
    (net (code "418") (name "unconnected-(P11-11-PadP$11)") (class "Default")
      (node (ref "P11") (pin "P$11") (pinfunction "11_P$11") (pintype "passive"))
    )
    (net (code "419") (name "unconnected-(P11-12-PadP$12)") (class "Default")
      (node (ref "P11") (pin "P$12") (pinfunction "12_P$12") (pintype "passive"))
    )
    (net (code "420") (name "unconnected-(P11-13-PadP$13)") (class "Default")
      (node (ref "P11") (pin "P$13") (pinfunction "13_P$13") (pintype "passive"))
    )
    (net (code "421") (name "unconnected-(P11-14-PadP$14)") (class "Default")
      (node (ref "P11") (pin "P$14") (pinfunction "14_P$14") (pintype "passive"))
    )
    (net (code "422") (name "unconnected-(P11-15-PadP$15)") (class "Default")
      (node (ref "P11") (pin "P$15") (pinfunction "15_P$15") (pintype "passive"))
    )
    (net (code "423") (name "unconnected-(P11-16-PadP$16)") (class "Default")
      (node (ref "P11") (pin "P$16") (pinfunction "16_P$16") (pintype "passive"))
    )
    (net (code "424") (name "unconnected-(P11-17-PadP$17)") (class "Default")
      (node (ref "P11") (pin "P$17") (pinfunction "17_P$17") (pintype "passive"))
    )
    (net (code "425") (name "unconnected-(P11-18-PadP$18)") (class "Default")
      (node (ref "P11") (pin "P$18") (pinfunction "18_P$18") (pintype "passive"))
    )
    (net (code "426") (name "unconnected-(P11-19-PadP$19)") (class "Default")
      (node (ref "P11") (pin "P$19") (pinfunction "19_P$19") (pintype "passive"))
    )
    (net (code "427") (name "unconnected-(P11-20-PadP$20)") (class "Default")
      (node (ref "P11") (pin "P$20") (pinfunction "20_P$20") (pintype "passive"))
    )
    (net (code "428") (name "unconnected-(P11-21-PadP$21)") (class "Default")
      (node (ref "P11") (pin "P$21") (pinfunction "21_P$21") (pintype "passive"))
    )
    (net (code "429") (name "unconnected-(P11-22-PadP$22)") (class "Default")
      (node (ref "P11") (pin "P$22") (pinfunction "22_P$22") (pintype "passive"))
    )
    (net (code "430") (name "unconnected-(P11-A-PadP$23)") (class "Default")
      (node (ref "P11") (pin "P$23") (pinfunction "A_P$23") (pintype "passive"))
    )
    (net (code "431") (name "unconnected-(P11-B-PadP$24)") (class "Default")
      (node (ref "P11") (pin "P$24") (pinfunction "B_P$24") (pintype "passive"))
    )
    (net (code "432") (name "unconnected-(P11-C-PadP$25)") (class "Default")
      (node (ref "P11") (pin "P$25") (pinfunction "C_P$25") (pintype "passive"))
    )
    (net (code "433") (name "unconnected-(P11-E-PadP$27)") (class "Default")
      (node (ref "P11") (pin "P$27") (pinfunction "E_P$27") (pintype "passive"))
    )
    (net (code "434") (name "unconnected-(P11-F-PadP$28)") (class "Default")
      (node (ref "P11") (pin "P$28") (pinfunction "F_P$28") (pintype "passive"))
    )
    (net (code "435") (name "unconnected-(P11-H-PadP$29)") (class "Default")
      (node (ref "P11") (pin "P$29") (pinfunction "H_P$29") (pintype "passive"))
    )
    (net (code "436") (name "unconnected-(P11-J-PadP$30)") (class "Default")
      (node (ref "P11") (pin "P$30") (pinfunction "J_P$30") (pintype "passive"))
    )
    (net (code "437") (name "unconnected-(P11-K-PadP$31)") (class "Default")
      (node (ref "P11") (pin "P$31") (pinfunction "K_P$31") (pintype "passive"))
    )
    (net (code "438") (name "unconnected-(P11-L-PadP$32)") (class "Default")
      (node (ref "P11") (pin "P$32") (pinfunction "L_P$32") (pintype "passive"))
    )
    (net (code "439") (name "unconnected-(P11-M-PadP$33)") (class "Default")
      (node (ref "P11") (pin "P$33") (pinfunction "M_P$33") (pintype "passive"))
    )
    (net (code "440") (name "unconnected-(P11-N-PadP$34)") (class "Default")
      (node (ref "P11") (pin "P$34") (pinfunction "N_P$34") (pintype "passive"))
    )
    (net (code "441") (name "unconnected-(P11-P-PadP$35)") (class "Default")
      (node (ref "P11") (pin "P$35") (pinfunction "P_P$35") (pintype "passive"))
    )
    (net (code "442") (name "unconnected-(P11-R-PadP$36)") (class "Default")
      (node (ref "P11") (pin "P$36") (pinfunction "R_P$36") (pintype "passive"))
    )
    (net (code "443") (name "unconnected-(P11-S-PadP$37)") (class "Default")
      (node (ref "P11") (pin "P$37") (pinfunction "S_P$37") (pintype "passive"))
    )
    (net (code "444") (name "unconnected-(P11-T-PadP$38)") (class "Default")
      (node (ref "P11") (pin "P$38") (pinfunction "T_P$38") (pintype "passive"))
    )
    (net (code "445") (name "unconnected-(P11-U-PadP$39)") (class "Default")
      (node (ref "P11") (pin "P$39") (pinfunction "U_P$39") (pintype "passive"))
    )
    (net (code "446") (name "unconnected-(P11-V-PadP$40)") (class "Default")
      (node (ref "P11") (pin "P$40") (pinfunction "V_P$40") (pintype "passive"))
    )
    (net (code "447") (name "unconnected-(P11-W-PadP$41)") (class "Default")
      (node (ref "P11") (pin "P$41") (pinfunction "W_P$41") (pintype "passive"))
    )
    (net (code "448") (name "unconnected-(P11-X-PadP$42)") (class "Default")
      (node (ref "P11") (pin "P$42") (pinfunction "X_P$42") (pintype "passive"))
    )
    (net (code "449") (name "unconnected-(P11-Y-PadP$43)") (class "Default")
      (node (ref "P11") (pin "P$43") (pinfunction "Y_P$43") (pintype "passive"))
    )
    (net (code "450") (name "unconnected-(P11-Z-PadP$44)") (class "Default")
      (node (ref "P11") (pin "P$44") (pinfunction "Z_P$44") (pintype "passive"))
    )
    (net (code "451") (name "unconnected-(P12-1-PadP$1)") (class "Default")
      (node (ref "P12") (pin "P$1") (pinfunction "1_P$1") (pintype "passive"))
    )
    (net (code "452") (name "unconnected-(P12-2-PadP$2)") (class "Default")
      (node (ref "P12") (pin "P$2") (pinfunction "2_P$2") (pintype "passive"))
    )
    (net (code "453") (name "unconnected-(P12-5-PadP$5)") (class "Default")
      (node (ref "P12") (pin "P$5") (pinfunction "5_P$5") (pintype "passive"))
    )
    (net (code "454") (name "unconnected-(P12-6-PadP$6)") (class "Default")
      (node (ref "P12") (pin "P$6") (pinfunction "6_P$6") (pintype "passive"))
    )
    (net (code "455") (name "unconnected-(P12-7-PadP$7)") (class "Default")
      (node (ref "P12") (pin "P$7") (pinfunction "7_P$7") (pintype "passive"))
    )
    (net (code "456") (name "unconnected-(P12-8-PadP$8)") (class "Default")
      (node (ref "P12") (pin "P$8") (pinfunction "8_P$8") (pintype "passive"))
    )
    (net (code "457") (name "unconnected-(P12-9-PadP$9)") (class "Default")
      (node (ref "P12") (pin "P$9") (pinfunction "9_P$9") (pintype "passive"))
    )
    (net (code "458") (name "unconnected-(P12-10-PadP$10)") (class "Default")
      (node (ref "P12") (pin "P$10") (pinfunction "10_P$10") (pintype "passive"))
    )
    (net (code "459") (name "unconnected-(P12-11-PadP$11)") (class "Default")
      (node (ref "P12") (pin "P$11") (pinfunction "11_P$11") (pintype "passive"))
    )
    (net (code "460") (name "unconnected-(P12-12-PadP$12)") (class "Default")
      (node (ref "P12") (pin "P$12") (pinfunction "12_P$12") (pintype "passive"))
    )
    (net (code "461") (name "unconnected-(P12-13-PadP$13)") (class "Default")
      (node (ref "P12") (pin "P$13") (pinfunction "13_P$13") (pintype "passive"))
    )
    (net (code "462") (name "unconnected-(P12-14-PadP$14)") (class "Default")
      (node (ref "P12") (pin "P$14") (pinfunction "14_P$14") (pintype "passive"))
    )
    (net (code "463") (name "unconnected-(P12-15-PadP$15)") (class "Default")
      (node (ref "P12") (pin "P$15") (pinfunction "15_P$15") (pintype "passive"))
    )
    (net (code "464") (name "unconnected-(P12-16-PadP$16)") (class "Default")
      (node (ref "P12") (pin "P$16") (pinfunction "16_P$16") (pintype "passive"))
    )
    (net (code "465") (name "unconnected-(P12-17-PadP$17)") (class "Default")
      (node (ref "P12") (pin "P$17") (pinfunction "17_P$17") (pintype "passive"))
    )
    (net (code "466") (name "unconnected-(P12-18-PadP$18)") (class "Default")
      (node (ref "P12") (pin "P$18") (pinfunction "18_P$18") (pintype "passive"))
    )
    (net (code "467") (name "unconnected-(P12-19-PadP$19)") (class "Default")
      (node (ref "P12") (pin "P$19") (pinfunction "19_P$19") (pintype "passive"))
    )
    (net (code "468") (name "unconnected-(P12-20-PadP$20)") (class "Default")
      (node (ref "P12") (pin "P$20") (pinfunction "20_P$20") (pintype "passive"))
    )
    (net (code "469") (name "unconnected-(P12-21-PadP$21)") (class "Default")
      (node (ref "P12") (pin "P$21") (pinfunction "21_P$21") (pintype "passive"))
    )
    (net (code "470") (name "unconnected-(P12-22-PadP$22)") (class "Default")
      (node (ref "P12") (pin "P$22") (pinfunction "22_P$22") (pintype "passive"))
    )
    (net (code "471") (name "unconnected-(P12-B-PadP$24)") (class "Default")
      (node (ref "P12") (pin "P$24") (pinfunction "B_P$24") (pintype "passive"))
    )
    (net (code "472") (name "unconnected-(P12-E-PadP$27)") (class "Default")
      (node (ref "P12") (pin "P$27") (pinfunction "E_P$27") (pintype "passive"))
    )
    (net (code "473") (name "unconnected-(P12-F-PadP$28)") (class "Default")
      (node (ref "P12") (pin "P$28") (pinfunction "F_P$28") (pintype "passive"))
    )
    (net (code "474") (name "unconnected-(P12-H-PadP$29)") (class "Default")
      (node (ref "P12") (pin "P$29") (pinfunction "H_P$29") (pintype "passive"))
    )
    (net (code "475") (name "unconnected-(P12-K-PadP$31)") (class "Default")
      (node (ref "P12") (pin "P$31") (pinfunction "K_P$31") (pintype "passive"))
    )
    (net (code "476") (name "unconnected-(P12-L-PadP$32)") (class "Default")
      (node (ref "P12") (pin "P$32") (pinfunction "L_P$32") (pintype "passive"))
    )
    (net (code "477") (name "unconnected-(P12-M-PadP$33)") (class "Default")
      (node (ref "P12") (pin "P$33") (pinfunction "M_P$33") (pintype "passive"))
    )
    (net (code "478") (name "unconnected-(P12-N-PadP$34)") (class "Default")
      (node (ref "P12") (pin "P$34") (pinfunction "N_P$34") (pintype "passive"))
    )
    (net (code "479") (name "unconnected-(P12-R-PadP$36)") (class "Default")
      (node (ref "P12") (pin "P$36") (pinfunction "R_P$36") (pintype "passive"))
    )
    (net (code "480") (name "unconnected-(P12-S-PadP$37)") (class "Default")
      (node (ref "P12") (pin "P$37") (pinfunction "S_P$37") (pintype "passive"))
    )
    (net (code "481") (name "unconnected-(P12-T-PadP$38)") (class "Default")
      (node (ref "P12") (pin "P$38") (pinfunction "T_P$38") (pintype "passive"))
    )
    (net (code "482") (name "unconnected-(P12-V-PadP$40)") (class "Default")
      (node (ref "P12") (pin "P$40") (pinfunction "V_P$40") (pintype "passive"))
    )
    (net (code "483") (name "unconnected-(P12-W-PadP$41)") (class "Default")
      (node (ref "P12") (pin "P$41") (pinfunction "W_P$41") (pintype "passive"))
    )
    (net (code "484") (name "unconnected-(P12-Y-PadP$43)") (class "Default")
      (node (ref "P12") (pin "P$43") (pinfunction "Y_P$43") (pintype "passive"))
    )
  )
)
